# duckypad.net
KiCad netlist of a schematic drawn in EAGLE
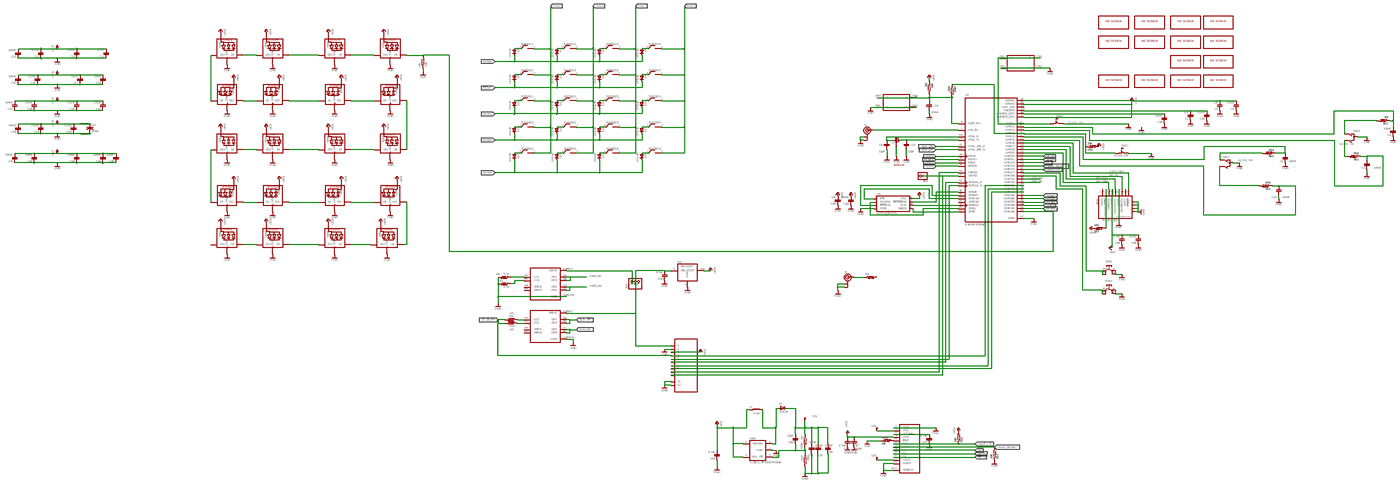
[diagram p0: schematic, sheet 1, overview]
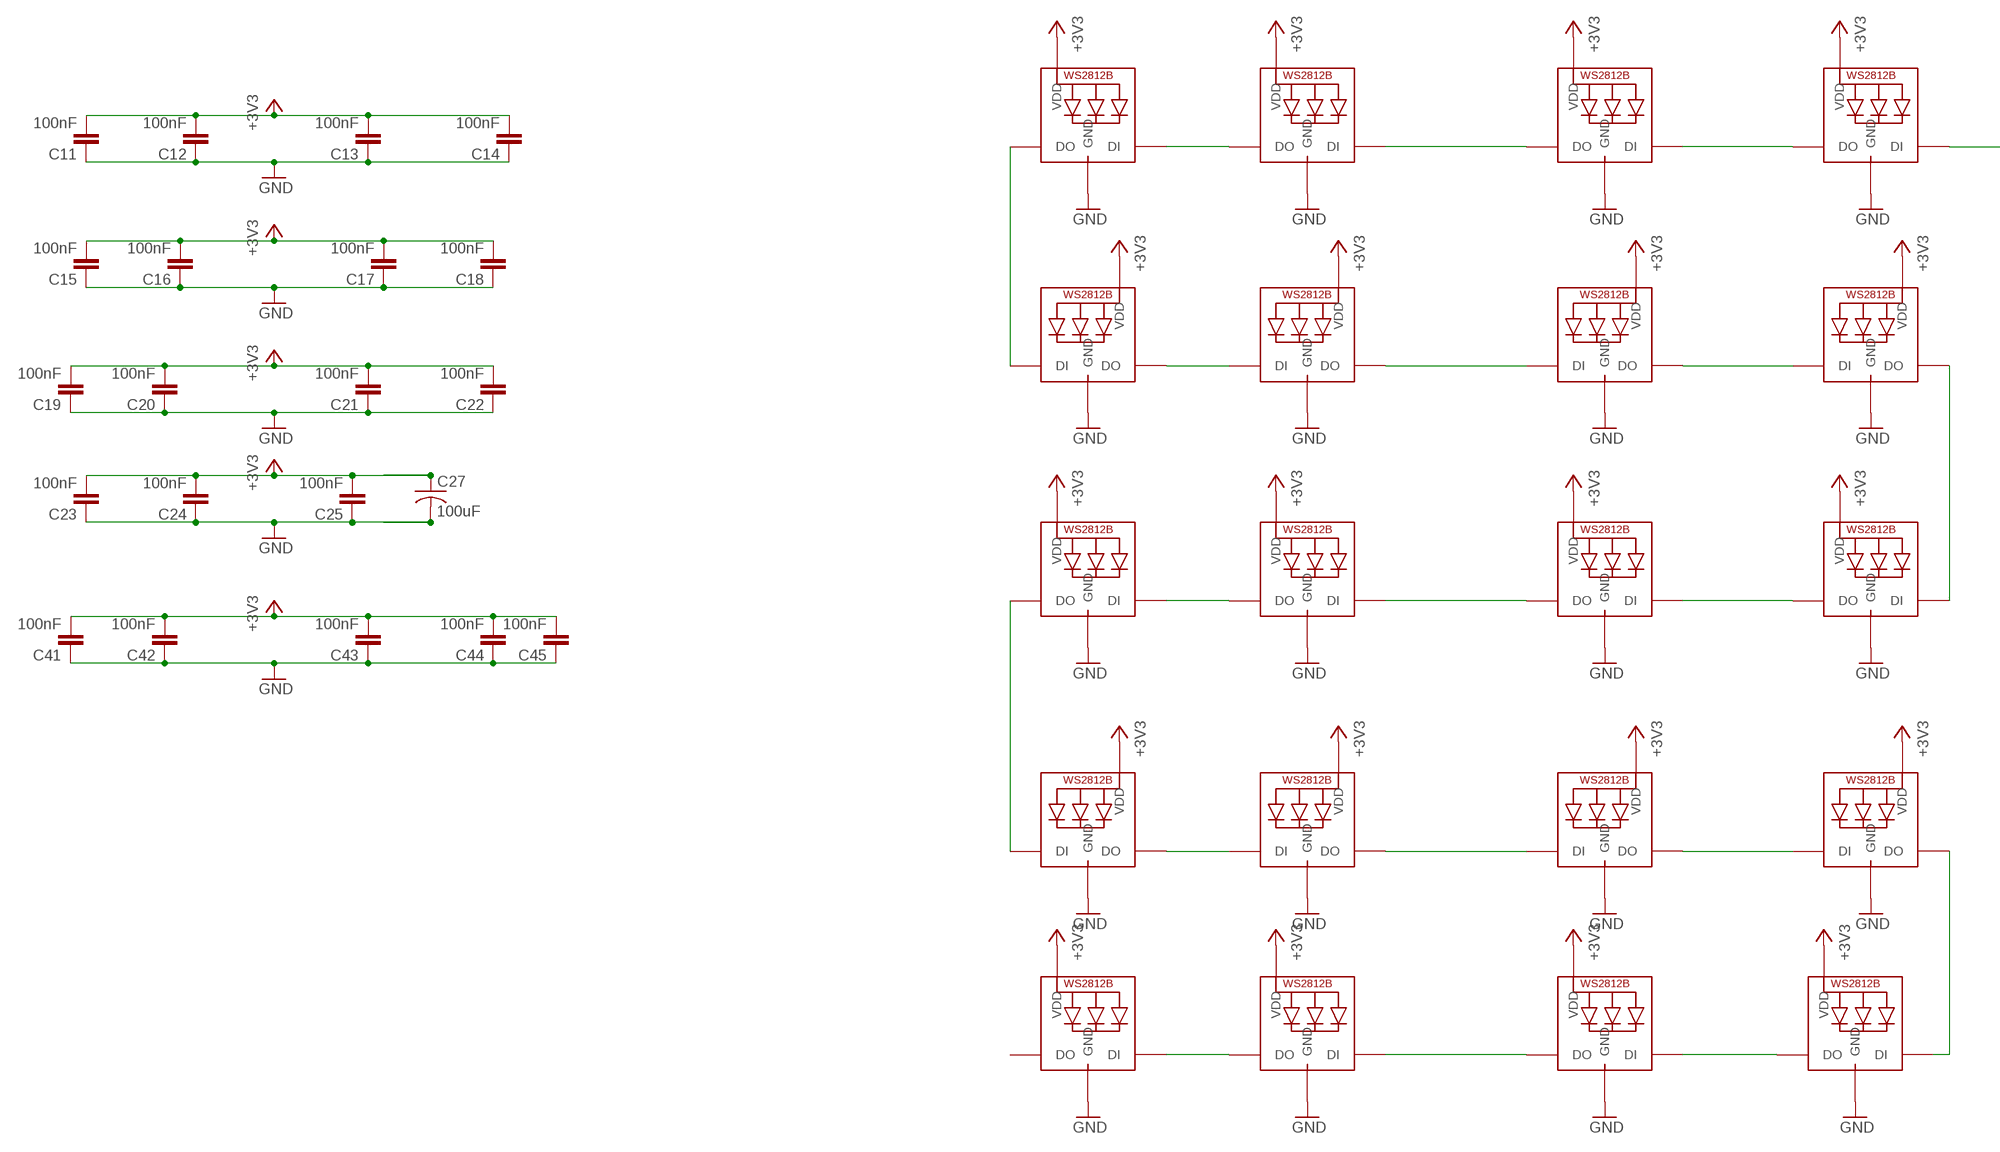
[diagram p1: schematic, sheet 1, part 1 of 4]
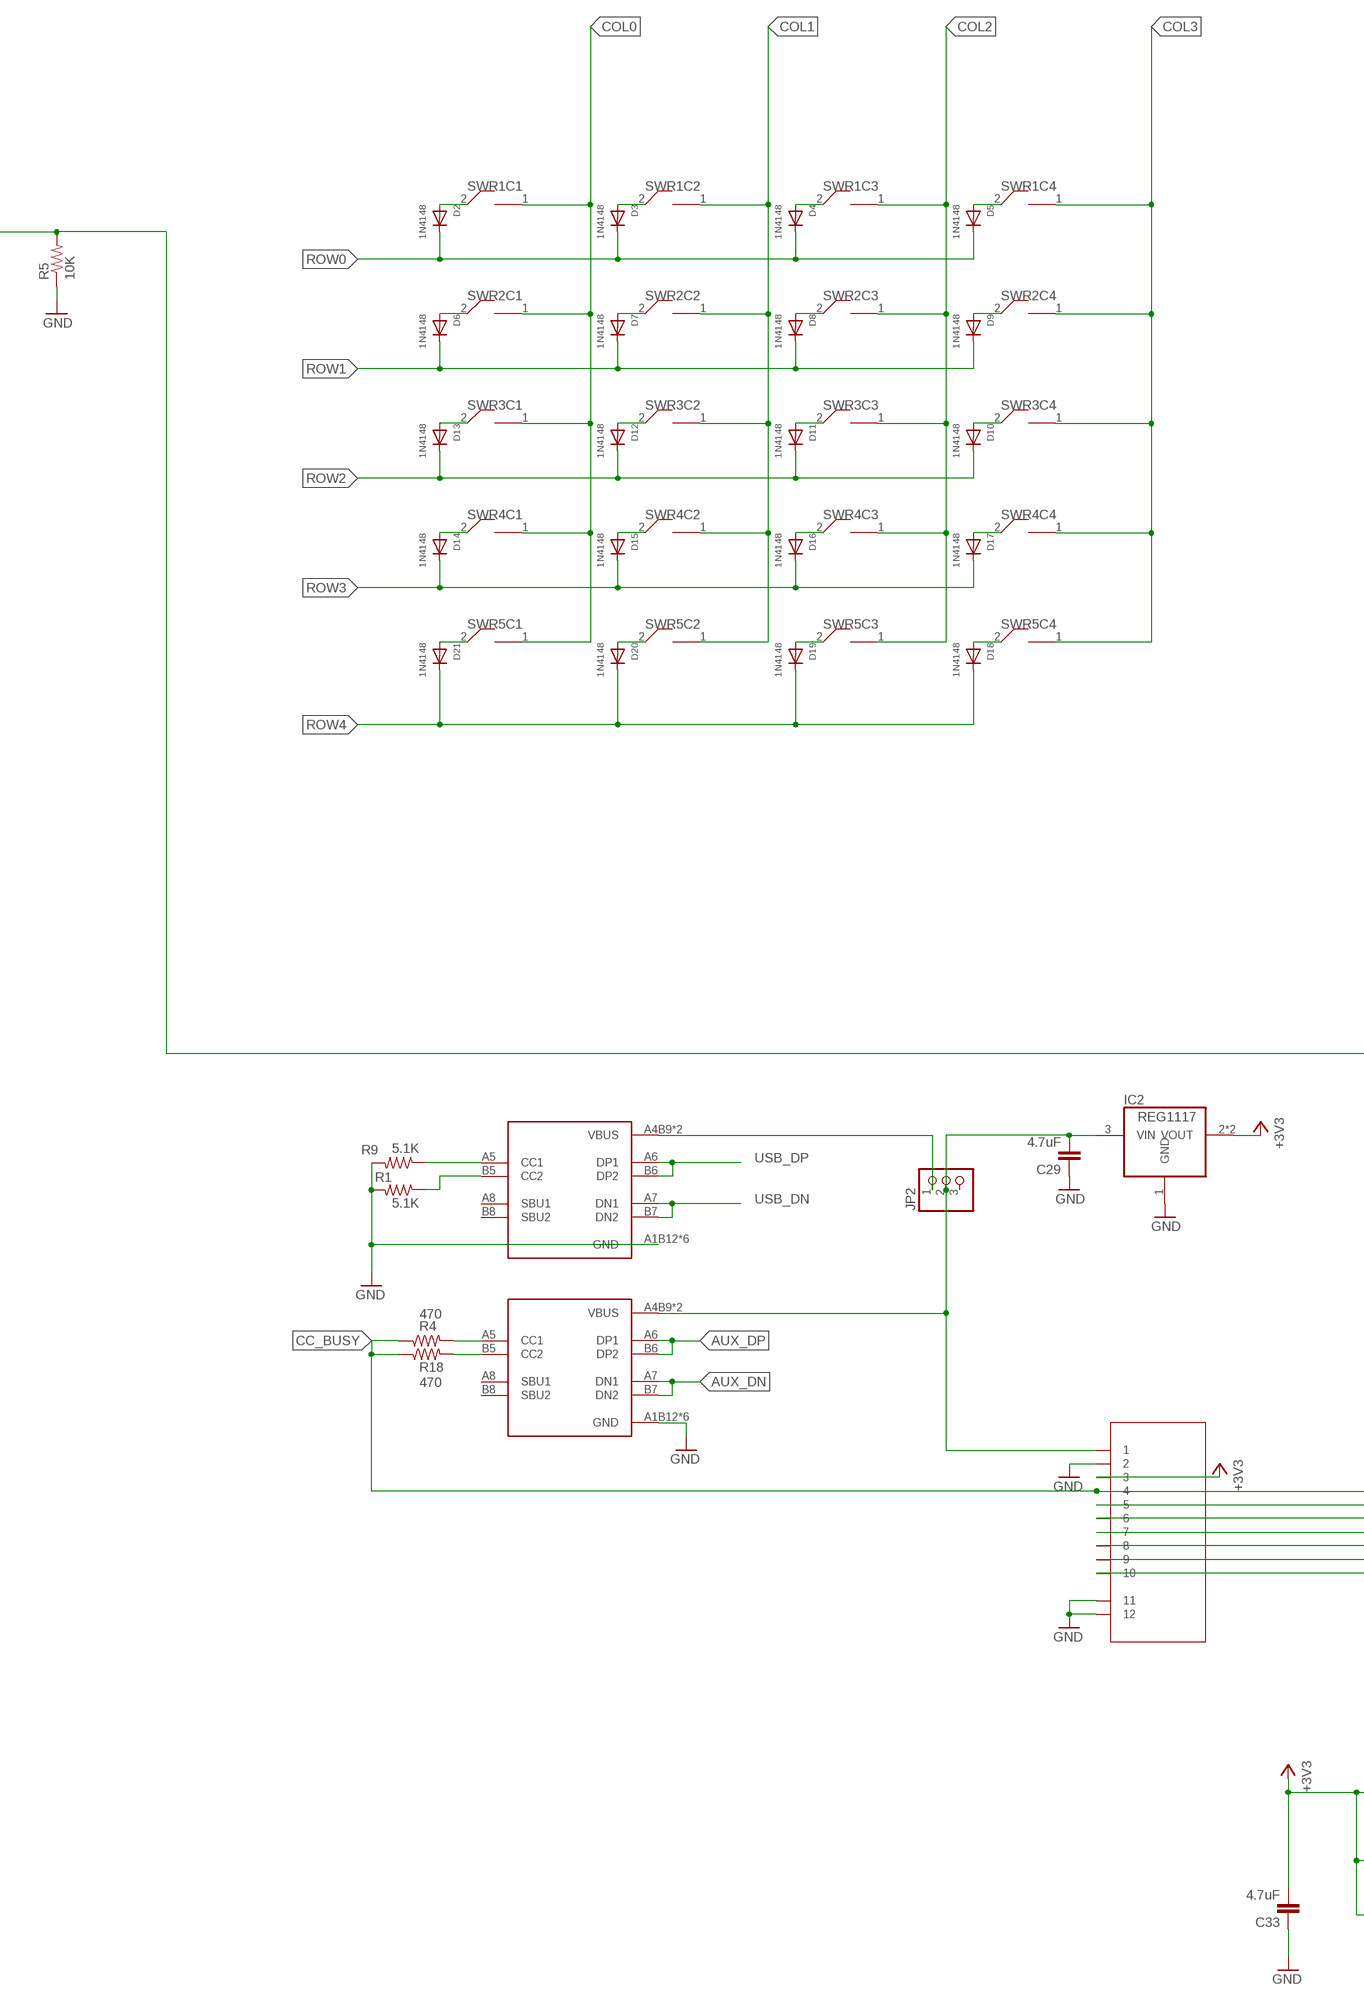
[diagram p2: schematic, sheet 1, part 2 of 4]
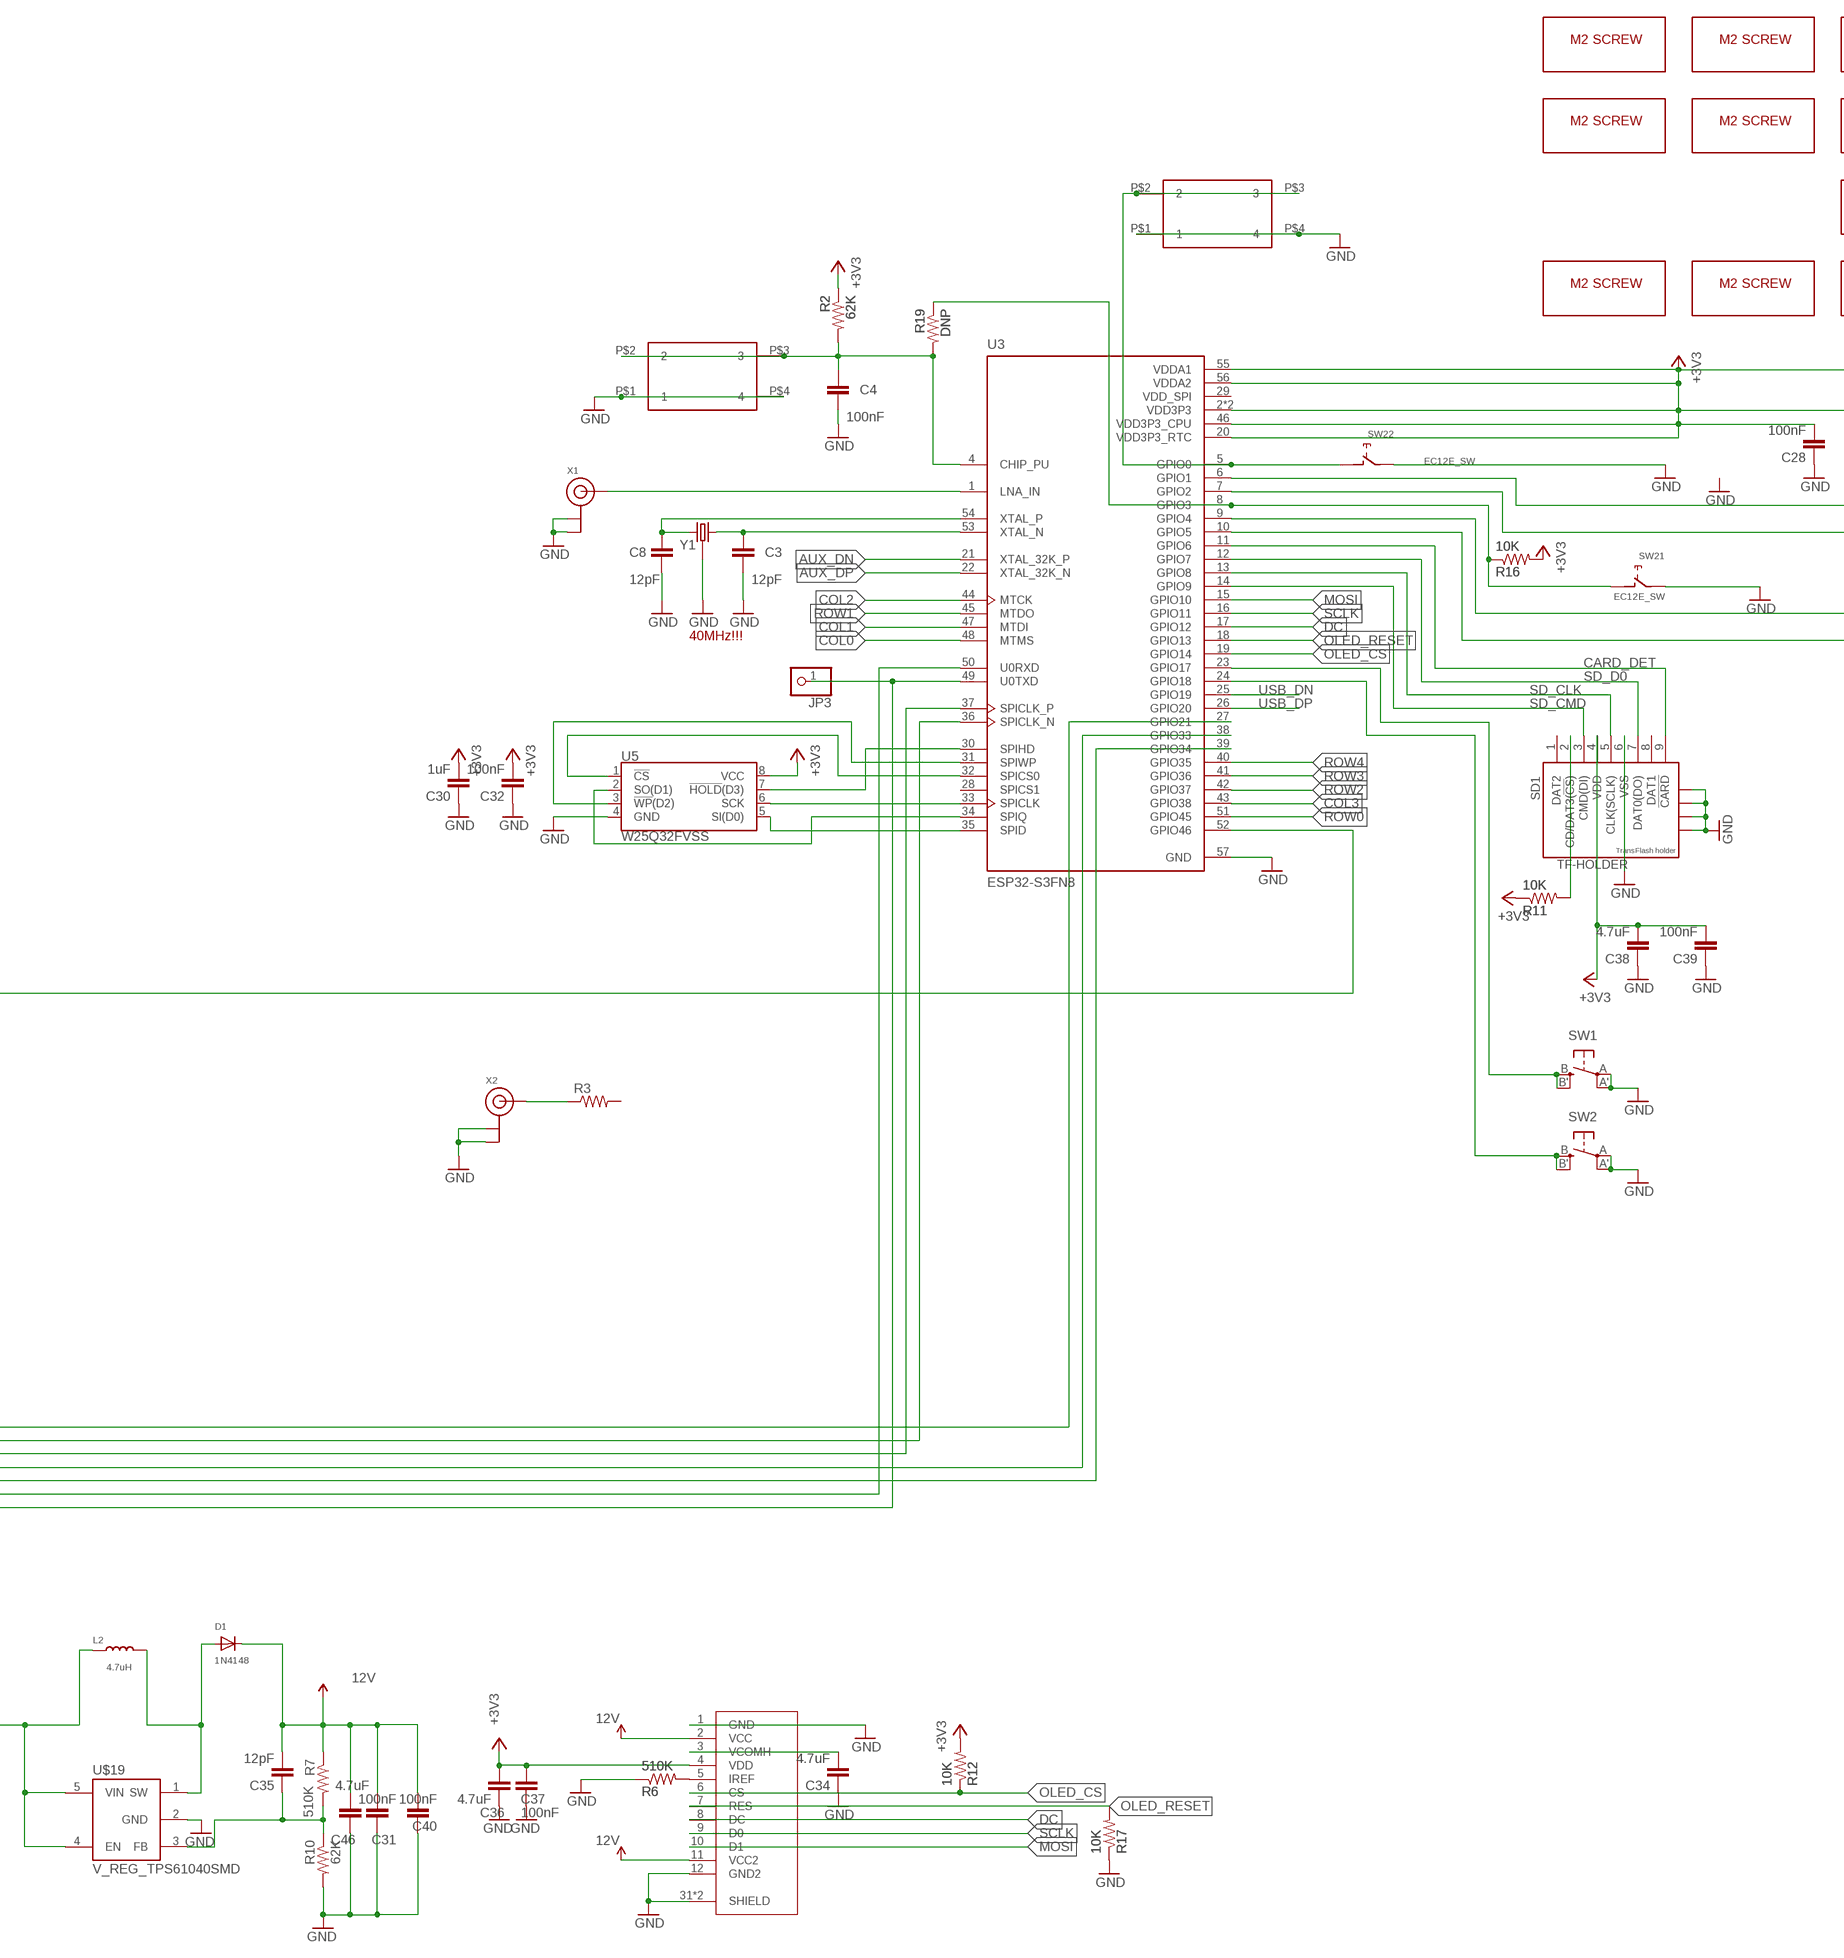
[diagram p3: schematic, sheet 1, part 3 of 4]
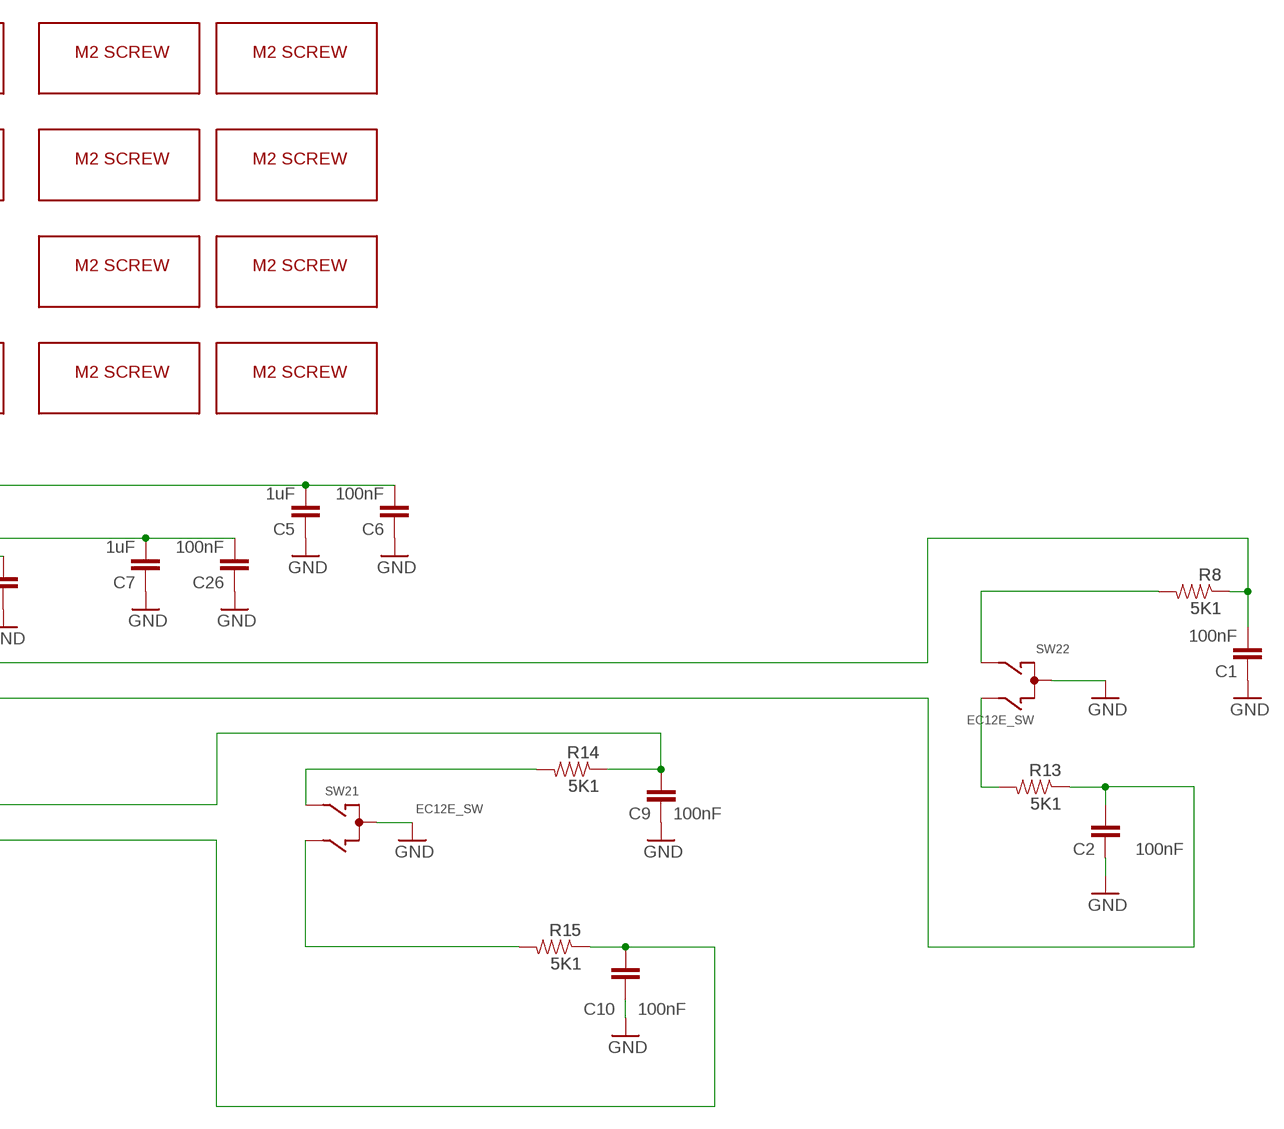
[diagram p4: schematic, sheet 1, part 4 of 4]

(export (version "E")
  (design (tool "Eeschema 10.0.6"))
  (components
    (comp (ref "C1")
      (value "100nF")
      (footprint "eagle-import:0805")
      (libsource (lib "eagle-import") (part "CAP0805"))
    )
    (comp (ref "C2")
      (value "100nF")
      (footprint "eagle-import:0805")
      (libsource (lib "eagle-import") (part "CAP0805"))
    )
    (comp (ref "C3")
      (value "12pF")
      (footprint "eagle-import:0805")
      (libsource (lib "eagle-import") (part "CAP0805"))
    )
    (comp (ref "C4")
      (value "100nF")
      (footprint "eagle-import:0805")
      (libsource (lib "eagle-import") (part "CAP0805"))
    )
    (comp (ref "C5")
      (value "1uF")
      (footprint "eagle-import:0805")
      (libsource (lib "eagle-import") (part "CAP0805"))
    )
    (comp (ref "C6")
      (value "100nF")
      (footprint "eagle-import:0805")
      (libsource (lib "eagle-import") (part "CAP0805"))
    )
    (comp (ref "C7")
      (value "1uF")
      (footprint "eagle-import:0805")
      (libsource (lib "eagle-import") (part "CAP0805"))
    )
    (comp (ref "C8")
      (value "12pF")
      (footprint "eagle-import:0805")
      (libsource (lib "eagle-import") (part "CAP0805"))
    )
    (comp (ref "C9")
      (value "100nF")
      (footprint "eagle-import:0805")
      (libsource (lib "eagle-import") (part "CAP0805"))
    )
    (comp (ref "C10")
      (value "100nF")
      (footprint "eagle-import:0805")
      (libsource (lib "eagle-import") (part "CAP0805"))
    )
    (comp (ref "C11")
      (value "100nF")
      (footprint "eagle-import:0805")
      (libsource (lib "eagle-import") (part "CAP0805"))
    )
    (comp (ref "C12")
      (value "100nF")
      (footprint "eagle-import:0805")
      (libsource (lib "eagle-import") (part "CAP0805"))
    )
    (comp (ref "C13")
      (value "100nF")
      (footprint "eagle-import:0805")
      (libsource (lib "eagle-import") (part "CAP0805"))
    )
    (comp (ref "C14")
      (value "100nF")
      (footprint "eagle-import:0805")
      (libsource (lib "eagle-import") (part "CAP0805"))
    )
    (comp (ref "C15")
      (value "100nF")
      (footprint "eagle-import:0805")
      (libsource (lib "eagle-import") (part "CAP0805"))
    )
    (comp (ref "C16")
      (value "100nF")
      (footprint "eagle-import:0805")
      (libsource (lib "eagle-import") (part "CAP0805"))
    )
    (comp (ref "C17")
      (value "100nF")
      (footprint "eagle-import:0805")
      (libsource (lib "eagle-import") (part "CAP0805"))
    )
    (comp (ref "C18")
      (value "100nF")
      (footprint "eagle-import:0805")
      (libsource (lib "eagle-import") (part "CAP0805"))
    )
    (comp (ref "C19")
      (value "100nF")
      (footprint "eagle-import:0805")
      (libsource (lib "eagle-import") (part "CAP0805"))
    )
    (comp (ref "C20")
      (value "100nF")
      (footprint "eagle-import:0805")
      (libsource (lib "eagle-import") (part "CAP0805"))
    )
    (comp (ref "C21")
      (value "100nF")
      (footprint "eagle-import:0805")
      (libsource (lib "eagle-import") (part "CAP0805"))
    )
    (comp (ref "C22")
      (value "100nF")
      (footprint "eagle-import:0805")
      (libsource (lib "eagle-import") (part "CAP0805"))
    )
    (comp (ref "C23")
      (value "100nF")
      (footprint "eagle-import:0805")
      (libsource (lib "eagle-import") (part "CAP0805"))
    )
    (comp (ref "C24")
      (value "100nF")
      (footprint "eagle-import:0805")
      (libsource (lib "eagle-import") (part "CAP0805"))
    )
    (comp (ref "C25")
      (value "100nF")
      (footprint "eagle-import:0805")
      (libsource (lib "eagle-import") (part "CAP0805"))
    )
    (comp (ref "C26")
      (value "100nF")
      (footprint "eagle-import:0805")
      (libsource (lib "eagle-import") (part "CAP0805"))
    )
    (comp (ref "C27")
      (value "100uF")
      (footprint "eagle-import:C1210")
      (libsource (lib "eagle-import") (part "C-USC1210"))
    )
    (comp (ref "C28")
      (value "100nF")
      (footprint "eagle-import:0805")
      (libsource (lib "eagle-import") (part "CAP0805"))
    )
    (comp (ref "C29")
      (value "4.7uF")
      (footprint "eagle-import:0805")
      (libsource (lib "eagle-import") (part "CAP0805"))
    )
    (comp (ref "C30")
      (value "1uF")
      (footprint "eagle-import:0805")
      (libsource (lib "eagle-import") (part "CAP0805"))
    )
    (comp (ref "C31")
      (value "100nF")
      (footprint "eagle-import:0805")
      (libsource (lib "eagle-import") (part "CAP0805"))
    )
    (comp (ref "C32")
      (value "100nF")
      (footprint "eagle-import:0805")
      (libsource (lib "eagle-import") (part "CAP0805"))
    )
    (comp (ref "C33")
      (value "4.7uF")
      (footprint "eagle-import:0805")
      (libsource (lib "eagle-import") (part "CAP0805"))
    )
    (comp (ref "C34")
      (value "4.7uF")
      (footprint "eagle-import:0805")
      (libsource (lib "eagle-import") (part "CAP0805"))
    )
    (comp (ref "C35")
      (value "12pF")
      (footprint "eagle-import:0805")
      (libsource (lib "eagle-import") (part "CAP0805"))
    )
    (comp (ref "C36")
      (value "4.7uF")
      (footprint "eagle-import:0805")
      (libsource (lib "eagle-import") (part "CAP0805"))
    )
    (comp (ref "C37")
      (value "100nF")
      (footprint "eagle-import:0805")
      (libsource (lib "eagle-import") (part "CAP0805"))
    )
    (comp (ref "C38")
      (value "4.7uF")
      (footprint "eagle-import:0805")
      (libsource (lib "eagle-import") (part "CAP0805"))
    )
    (comp (ref "C39")
      (value "100nF")
      (footprint "eagle-import:0805")
      (libsource (lib "eagle-import") (part "CAP0805"))
    )
    (comp (ref "C40")
      (value "100nF")
      (footprint "eagle-import:0805")
      (libsource (lib "eagle-import") (part "CAP0805"))
    )
    (comp (ref "C41")
      (value "100nF")
      (footprint "eagle-import:0805")
      (libsource (lib "eagle-import") (part "CAP0805"))
    )
    (comp (ref "C42")
      (value "100nF")
      (footprint "eagle-import:0805")
      (libsource (lib "eagle-import") (part "CAP0805"))
    )
    (comp (ref "C43")
      (value "100nF")
      (footprint "eagle-import:0805")
      (libsource (lib "eagle-import") (part "CAP0805"))
    )
    (comp (ref "C44")
      (value "100nF")
      (footprint "eagle-import:0805")
      (libsource (lib "eagle-import") (part "CAP0805"))
    )
    (comp (ref "C45")
      (value "100nF")
      (footprint "eagle-import:0805")
      (libsource (lib "eagle-import") (part "CAP0805"))
    )
    (comp (ref "C46")
      (value "4.7uF")
      (footprint "eagle-import:0805")
      (libsource (lib "eagle-import") (part "CAP0805"))
    )
    (comp (ref "D1")
      (value "1N4148")
      (footprint "eagle-import:ADAFRUIT_CHANGED_SOD-123")
      (libsource (lib "eagle-import") (part "ADAFRUIT_CHANGED_DIODESOD-123"))
    )
    (comp (ref "D2")
      (value "1N4148")
      (footprint "eagle-import:ADAFRUIT_CHANGED_SOD-123")
      (libsource (lib "eagle-import") (part "ADAFRUIT_CHANGED_DIODESOD-123"))
    )
    (comp (ref "D3")
      (value "1N4148")
      (footprint "eagle-import:ADAFRUIT_CHANGED_SOD-123")
      (libsource (lib "eagle-import") (part "ADAFRUIT_CHANGED_DIODESOD-123"))
    )
    (comp (ref "D4")
      (value "1N4148")
      (footprint "eagle-import:ADAFRUIT_CHANGED_SOD-123")
      (libsource (lib "eagle-import") (part "ADAFRUIT_CHANGED_DIODESOD-123"))
    )
    (comp (ref "D5")
      (value "1N4148")
      (footprint "eagle-import:ADAFRUIT_CHANGED_SOD-123")
      (libsource (lib "eagle-import") (part "ADAFRUIT_CHANGED_DIODESOD-123"))
    )
    (comp (ref "D6")
      (value "1N4148")
      (footprint "eagle-import:ADAFRUIT_CHANGED_SOD-123")
      (libsource (lib "eagle-import") (part "ADAFRUIT_CHANGED_DIODESOD-123"))
    )
    (comp (ref "D7")
      (value "1N4148")
      (footprint "eagle-import:ADAFRUIT_CHANGED_SOD-123")
      (libsource (lib "eagle-import") (part "ADAFRUIT_CHANGED_DIODESOD-123"))
    )
    (comp (ref "D8")
      (value "1N4148")
      (footprint "eagle-import:ADAFRUIT_CHANGED_SOD-123")
      (libsource (lib "eagle-import") (part "ADAFRUIT_CHANGED_DIODESOD-123"))
    )
    (comp (ref "D9")
      (value "1N4148")
      (footprint "eagle-import:ADAFRUIT_CHANGED_SOD-123")
      (libsource (lib "eagle-import") (part "ADAFRUIT_CHANGED_DIODESOD-123"))
    )
    (comp (ref "D10")
      (value "1N4148")
      (footprint "eagle-import:ADAFRUIT_CHANGED_SOD-123")
      (libsource (lib "eagle-import") (part "ADAFRUIT_CHANGED_DIODESOD-123"))
    )
    (comp (ref "D11")
      (value "1N4148")
      (footprint "eagle-import:ADAFRUIT_CHANGED_SOD-123")
      (libsource (lib "eagle-import") (part "ADAFRUIT_CHANGED_DIODESOD-123"))
    )
    (comp (ref "D12")
      (value "1N4148")
      (footprint "eagle-import:ADAFRUIT_CHANGED_SOD-123")
      (libsource (lib "eagle-import") (part "ADAFRUIT_CHANGED_DIODESOD-123"))
    )
    (comp (ref "D13")
      (value "1N4148")
      (footprint "eagle-import:ADAFRUIT_CHANGED_SOD-123")
      (libsource (lib "eagle-import") (part "ADAFRUIT_CHANGED_DIODESOD-123"))
    )
    (comp (ref "D14")
      (value "1N4148")
      (footprint "eagle-import:ADAFRUIT_CHANGED_SOD-123")
      (libsource (lib "eagle-import") (part "ADAFRUIT_CHANGED_DIODESOD-123"))
    )
    (comp (ref "D15")
      (value "1N4148")
      (footprint "eagle-import:ADAFRUIT_CHANGED_SOD-123")
      (libsource (lib "eagle-import") (part "ADAFRUIT_CHANGED_DIODESOD-123"))
    )
    (comp (ref "D16")
      (value "1N4148")
      (footprint "eagle-import:ADAFRUIT_CHANGED_SOD-123")
      (libsource (lib "eagle-import") (part "ADAFRUIT_CHANGED_DIODESOD-123"))
    )
    (comp (ref "D17")
      (value "1N4148")
      (footprint "eagle-import:ADAFRUIT_CHANGED_SOD-123")
      (libsource (lib "eagle-import") (part "ADAFRUIT_CHANGED_DIODESOD-123"))
    )
    (comp (ref "D18")
      (value "1N4148")
      (footprint "eagle-import:ADAFRUIT_CHANGED_SOD-123")
      (libsource (lib "eagle-import") (part "ADAFRUIT_CHANGED_DIODESOD-123"))
    )
    (comp (ref "D19")
      (value "1N4148")
      (footprint "eagle-import:ADAFRUIT_CHANGED_SOD-123")
      (libsource (lib "eagle-import") (part "ADAFRUIT_CHANGED_DIODESOD-123"))
    )
    (comp (ref "D20")
      (value "1N4148")
      (footprint "eagle-import:ADAFRUIT_CHANGED_SOD-123")
      (libsource (lib "eagle-import") (part "ADAFRUIT_CHANGED_DIODESOD-123"))
    )
    (comp (ref "D21")
      (value "1N4148")
      (footprint "eagle-import:ADAFRUIT_CHANGED_SOD-123")
      (libsource (lib "eagle-import") (part "ADAFRUIT_CHANGED_DIODESOD-123"))
    )
    (comp (ref "IC2")
      (value "REG1117")
      (footprint "eagle-import:SOT223")
      (libsource (lib "eagle-import") (part "REG1117"))
    )
    (comp (ref "JP2")
      (value "PINHD-1X3CB")
      (footprint "eagle-import:1X03-CLEANBIG")
      (libsource (lib "eagle-import") (part "PINHD-1X3CB"))
    )
    (comp (ref "JP3")
      (value "PINHD-1X1CB")
      (footprint "eagle-import:1X01-CLEANBIG")
      (libsource (lib "eagle-import") (part "PINHD-1X1CB"))
    )
    (comp (ref "L2")
      (value "4.7uH")
      (footprint "eagle-import:L4030")
      (libsource (lib "eagle-import") (part "L-4030"))
    )
    (comp (ref "LED_R1C1")
      (value "WS2812B")
      (footprint "eagle-import:REVERSE_MNT")
      (libsource (lib "eagle-import") (part "WS2812B"))
    )
    (comp (ref "LED_R1C2")
      (value "WS2812B")
      (footprint "eagle-import:REVERSE_MNT")
      (libsource (lib "eagle-import") (part "WS2812B"))
    )
    (comp (ref "LED_R1C3")
      (value "WS2812B")
      (footprint "eagle-import:REVERSE_MNT")
      (libsource (lib "eagle-import") (part "WS2812B"))
    )
    (comp (ref "LED_R1C4")
      (value "WS2812B")
      (footprint "eagle-import:REVERSE_MNT")
      (libsource (lib "eagle-import") (part "WS2812B"))
    )
    (comp (ref "LED_R2C1")
      (value "WS2812B")
      (footprint "eagle-import:REVERSE_MNT")
      (libsource (lib "eagle-import") (part "WS2812B"))
    )
    (comp (ref "LED_R2C2")
      (value "WS2812B")
      (footprint "eagle-import:REVERSE_MNT")
      (libsource (lib "eagle-import") (part "WS2812B"))
    )
    (comp (ref "LED_R2C3")
      (value "WS2812B")
      (footprint "eagle-import:REVERSE_MNT")
      (libsource (lib "eagle-import") (part "WS2812B"))
    )
    (comp (ref "LED_R2C4")
      (value "WS2812B")
      (footprint "eagle-import:REVERSE_MNT")
      (libsource (lib "eagle-import") (part "WS2812B"))
    )
    (comp (ref "LED_R3C1")
      (value "WS2812B")
      (footprint "eagle-import:REVERSE_MNT")
      (libsource (lib "eagle-import") (part "WS2812B"))
    )
    (comp (ref "LED_R3C2")
      (value "WS2812B")
      (footprint "eagle-import:REVERSE_MNT")
      (libsource (lib "eagle-import") (part "WS2812B"))
    )
    (comp (ref "LED_R3C3")
      (value "WS2812B")
      (footprint "eagle-import:REVERSE_MNT")
      (libsource (lib "eagle-import") (part "WS2812B"))
    )
    (comp (ref "LED_R3C4")
      (value "WS2812B")
      (footprint "eagle-import:REVERSE_MNT")
      (libsource (lib "eagle-import") (part "WS2812B"))
    )
    (comp (ref "LED_R4C1")
      (value "WS2812B")
      (footprint "eagle-import:REVERSE_MNT")
      (libsource (lib "eagle-import") (part "WS2812B"))
    )
    (comp (ref "LED_R4C2")
      (value "WS2812B")
      (footprint "eagle-import:REVERSE_MNT")
      (libsource (lib "eagle-import") (part "WS2812B"))
    )
    (comp (ref "LED_R4C3")
      (value "WS2812B")
      (footprint "eagle-import:REVERSE_MNT")
      (libsource (lib "eagle-import") (part "WS2812B"))
    )
    (comp (ref "LED_R4C4")
      (value "WS2812B")
      (footprint "eagle-import:REVERSE_MNT")
      (libsource (lib "eagle-import") (part "WS2812B"))
    )
    (comp (ref "LED_R5C1")
      (value "WS2812B")
      (footprint "eagle-import:REVERSE_MNT")
      (libsource (lib "eagle-import") (part "WS2812B"))
    )
    (comp (ref "LED_R5C2")
      (value "WS2812B")
      (footprint "eagle-import:REVERSE_MNT")
      (libsource (lib "eagle-import") (part "WS2812B"))
    )
    (comp (ref "LED_R5C3")
      (value "WS2812B")
      (footprint "eagle-import:REVERSE_MNT")
      (libsource (lib "eagle-import") (part "WS2812B"))
    )
    (comp (ref "LED_R5C4")
      (value "WS2812B")
      (footprint "eagle-import:REVERSE_MNT")
      (libsource (lib "eagle-import") (part "WS2812B"))
    )
    (comp (ref "R1")
      (value "5.1K")
      (footprint "eagle-import:0805")
      (libsource (lib "eagle-import") (part "joyAnalog_RESISTOR0805-RES"))
    )
    (comp (ref "R2")
      (value "62K")
      (footprint "eagle-import:0805")
      (libsource (lib "eagle-import") (part "joyAnalog_RESISTOR0805-RES"))
    )
    (comp (ref "R3")
      (value "R-US_R2010")
      (footprint "eagle-import:R2010")
      (libsource (lib "eagle-import") (part "R-US_R2010"))
    )
    (comp (ref "R4")
      (value "470")
      (footprint "eagle-import:0805")
      (libsource (lib "eagle-import") (part "joyAnalog_RESISTOR0805-RES"))
    )
    (comp (ref "R5")
      (value "10K")
      (footprint "eagle-import:0805")
      (libsource (lib "eagle-import") (part "RESISTOR0805-RES"))
    )
    (comp (ref "R6")
      (value "510K")
      (footprint "eagle-import:0805")
      (libsource (lib "eagle-import") (part "joyAnalog_RESISTOR0805-RES"))
    )
    (comp (ref "R7")
      (value "510K")
      (footprint "eagle-import:0805")
      (libsource (lib "eagle-import") (part "joyAnalog_RESISTOR0805-RES"))
    )
    (comp (ref "R8")
      (value "5K1")
      (footprint "eagle-import:0805")
      (libsource (lib "eagle-import") (part "joyAnalog_RESISTOR0805-RES"))
    )
    (comp (ref "R9")
      (value "5.1K")
      (footprint "eagle-import:0805")
      (libsource (lib "eagle-import") (part "joyAnalog_RESISTOR0805-RES"))
    )
    (comp (ref "R10")
      (value "62K")
      (footprint "eagle-import:0805")
      (libsource (lib "eagle-import") (part "joyAnalog_RESISTOR0805-RES"))
    )
    (comp (ref "R11")
      (value "10K")
      (footprint "eagle-import:0805")
      (libsource (lib "eagle-import") (part "joyAnalog_RESISTOR0805-RES"))
    )
    (comp (ref "R12")
      (value "10K")
      (footprint "eagle-import:0805")
      (libsource (lib "eagle-import") (part "joyAnalog_RESISTOR0805-RES"))
    )
    (comp (ref "R13")
      (value "5K1")
      (footprint "eagle-import:0805")
      (libsource (lib "eagle-import") (part "joyAnalog_RESISTOR0805-RES"))
    )
    (comp (ref "R14")
      (value "5K1")
      (footprint "eagle-import:0805")
      (libsource (lib "eagle-import") (part "joyAnalog_RESISTOR0805-RES"))
    )
    (comp (ref "R15")
      (value "5K1")
      (footprint "eagle-import:0805")
      (libsource (lib "eagle-import") (part "joyAnalog_RESISTOR0805-RES"))
    )
    (comp (ref "R16")
      (value "10K")
      (footprint "eagle-import:0805")
      (libsource (lib "eagle-import") (part "joyAnalog_RESISTOR0805-RES"))
    )
    (comp (ref "R17")
      (value "10K")
      (footprint "eagle-import:0805")
      (libsource (lib "eagle-import") (part "joyAnalog_RESISTOR0805-RES"))
    )
    (comp (ref "R18")
      (value "470")
      (footprint "eagle-import:0805")
      (libsource (lib "eagle-import") (part "joyAnalog_RESISTOR0805-RES"))
    )
    (comp (ref "R19")
      (value "DNP")
      (footprint "eagle-import:0805")
      (libsource (lib "eagle-import") (part "joyAnalog_RESISTOR0805-RES"))
    )
    (comp (ref "SD1")
      (value "TF-HOLDER")
      (footprint "eagle-import:TF-PULL")
      (libsource (lib "eagle-import") (part "TF-HOLDER"))
    )
    (comp (ref "SW1")
      (value "SPST_TACT-EVQQ2")
      (footprint "eagle-import:EVQ-Q2")
      (libsource (lib "eagle-import") (part "SPST_TACT-EVQQ2"))
    )
    (comp (ref "SW2")
      (value "SPST_TACT-EVQQ2")
      (footprint "eagle-import:EVQ-Q2")
      (libsource (lib "eagle-import") (part "SPST_TACT-EVQQ2"))
    )
    (comp (ref "SW3")
      (value "324_SW324_SWITCH_FOOT_HOLE")
      (footprint "eagle-import:342_SWICH_FOOT_HOLE")
      (libsource (lib "eagle-import") (part "324_SW324_SWITCH_FOOT_HOLE"))
    )
    (comp (ref "SW4")
      (value "324_SW324_SWITCH_FOOT_HOLE")
      (footprint "eagle-import:342_SWICH_FOOT_HOLE")
      (libsource (lib "eagle-import") (part "324_SW324_SWITCH_FOOT_HOLE"))
    )
    (comp (ref "SW21")
      (value "EC12E_SW")
      (footprint "eagle-import:ALPS_EC12E_SW")
      (fields (field (name "MPN") "EC12E2424407"))
      (libsource (lib "eagle-import") (part "EC12E_SW"))
    )
    (comp (ref "SW22")
      (value "EC12E_SW")
      (footprint "eagle-import:ALPS_EC12E_SW")
      (fields (field (name "MPN") "EC12E2424407"))
      (libsource (lib "eagle-import") (part "EC12E_SW"))
    )
    (comp (ref "SWR1C1")
      (value "KAILH_SWITCH_SOCKET_KAILH_SWITCH_SOCKET")
      (footprint "eagle-import:KAILH_SWITCH_SOCKET_SWITCH_SOCKET")
      (libsource (lib "eagle-import") (part "KAILH_SWITCH_SOCKET_KAILH_SWITCH_SOCKET"))
    )
    (comp (ref "SWR1C2")
      (value "KAILH_SWITCH_SOCKET_KAILH_SWITCH_SOCKET")
      (footprint "eagle-import:KAILH_SWITCH_SOCKET_SWITCH_SOCKET")
      (libsource (lib "eagle-import") (part "KAILH_SWITCH_SOCKET_KAILH_SWITCH_SOCKET"))
    )
    (comp (ref "SWR1C3")
      (value "KAILH_SWITCH_SOCKET_KAILH_SWITCH_SOCKET")
      (footprint "eagle-import:KAILH_SWITCH_SOCKET_SWITCH_SOCKET")
      (libsource (lib "eagle-import") (part "KAILH_SWITCH_SOCKET_KAILH_SWITCH_SOCKET"))
    )
    (comp (ref "SWR1C4")
      (value "KAILH_SWITCH_SOCKET_KAILH_SWITCH_SOCKET")
      (footprint "eagle-import:KAILH_SWITCH_SOCKET_SWITCH_SOCKET")
      (libsource (lib "eagle-import") (part "KAILH_SWITCH_SOCKET_KAILH_SWITCH_SOCKET"))
    )
    (comp (ref "SWR2C1")
      (value "KAILH_SWITCH_SOCKET_KAILH_SWITCH_SOCKET")
      (footprint "eagle-import:KAILH_SWITCH_SOCKET_SWITCH_SOCKET")
      (libsource (lib "eagle-import") (part "KAILH_SWITCH_SOCKET_KAILH_SWITCH_SOCKET"))
    )
    (comp (ref "SWR2C2")
      (value "KAILH_SWITCH_SOCKET_KAILH_SWITCH_SOCKET")
      (footprint "eagle-import:KAILH_SWITCH_SOCKET_SWITCH_SOCKET")
      (libsource (lib "eagle-import") (part "KAILH_SWITCH_SOCKET_KAILH_SWITCH_SOCKET"))
    )
    (comp (ref "SWR2C3")
      (value "KAILH_SWITCH_SOCKET_KAILH_SWITCH_SOCKET")
      (footprint "eagle-import:KAILH_SWITCH_SOCKET_SWITCH_SOCKET")
      (libsource (lib "eagle-import") (part "KAILH_SWITCH_SOCKET_KAILH_SWITCH_SOCKET"))
    )
    (comp (ref "SWR2C4")
      (value "KAILH_SWITCH_SOCKET_KAILH_SWITCH_SOCKET")
      (footprint "eagle-import:KAILH_SWITCH_SOCKET_SWITCH_SOCKET")
      (libsource (lib "eagle-import") (part "KAILH_SWITCH_SOCKET_KAILH_SWITCH_SOCKET"))
    )
    (comp (ref "SWR3C1")
      (value "KAILH_SWITCH_SOCKET_KAILH_SWITCH_SOCKET")
      (footprint "eagle-import:KAILH_SWITCH_SOCKET_SWITCH_SOCKET")
      (libsource (lib "eagle-import") (part "KAILH_SWITCH_SOCKET_KAILH_SWITCH_SOCKET"))
    )
    (comp (ref "SWR3C2")
      (value "KAILH_SWITCH_SOCKET_KAILH_SWITCH_SOCKET")
      (footprint "eagle-import:KAILH_SWITCH_SOCKET_SWITCH_SOCKET")
      (libsource (lib "eagle-import") (part "KAILH_SWITCH_SOCKET_KAILH_SWITCH_SOCKET"))
    )
    (comp (ref "SWR3C3")
      (value "KAILH_SWITCH_SOCKET_KAILH_SWITCH_SOCKET")
      (footprint "eagle-import:KAILH_SWITCH_SOCKET_SWITCH_SOCKET")
      (libsource (lib "eagle-import") (part "KAILH_SWITCH_SOCKET_KAILH_SWITCH_SOCKET"))
    )
    (comp (ref "SWR3C4")
      (value "KAILH_SWITCH_SOCKET_KAILH_SWITCH_SOCKET")
      (footprint "eagle-import:KAILH_SWITCH_SOCKET_SWITCH_SOCKET")
      (libsource (lib "eagle-import") (part "KAILH_SWITCH_SOCKET_KAILH_SWITCH_SOCKET"))
    )
    (comp (ref "SWR4C1")
      (value "KAILH_SWITCH_SOCKET_KAILH_SWITCH_SOCKET")
      (footprint "eagle-import:KAILH_SWITCH_SOCKET_SWITCH_SOCKET")
      (libsource (lib "eagle-import") (part "KAILH_SWITCH_SOCKET_KAILH_SWITCH_SOCKET"))
    )
    (comp (ref "SWR4C2")
      (value "KAILH_SWITCH_SOCKET_KAILH_SWITCH_SOCKET")
      (footprint "eagle-import:KAILH_SWITCH_SOCKET_SWITCH_SOCKET")
      (libsource (lib "eagle-import") (part "KAILH_SWITCH_SOCKET_KAILH_SWITCH_SOCKET"))
    )
    (comp (ref "SWR4C3")
      (value "KAILH_SWITCH_SOCKET_KAILH_SWITCH_SOCKET")
      (footprint "eagle-import:KAILH_SWITCH_SOCKET_SWITCH_SOCKET")
      (libsource (lib "eagle-import") (part "KAILH_SWITCH_SOCKET_KAILH_SWITCH_SOCKET"))
    )
    (comp (ref "SWR4C4")
      (value "KAILH_SWITCH_SOCKET_KAILH_SWITCH_SOCKET")
      (footprint "eagle-import:KAILH_SWITCH_SOCKET_SWITCH_SOCKET")
      (libsource (lib "eagle-import") (part "KAILH_SWITCH_SOCKET_KAILH_SWITCH_SOCKET"))
    )
    (comp (ref "SWR5C1")
      (value "KAILH_SWITCH_SOCKET_KAILH_SWITCH_SOCKET")
      (footprint "eagle-import:KAILH_SWITCH_SOCKET_SWITCH_SOCKET")
      (libsource (lib "eagle-import") (part "KAILH_SWITCH_SOCKET_KAILH_SWITCH_SOCKET"))
    )
    (comp (ref "SWR5C2")
      (value "KAILH_SWITCH_SOCKET_KAILH_SWITCH_SOCKET")
      (footprint "eagle-import:KAILH_SWITCH_SOCKET_SWITCH_SOCKET")
      (libsource (lib "eagle-import") (part "KAILH_SWITCH_SOCKET_KAILH_SWITCH_SOCKET"))
    )
    (comp (ref "SWR5C3")
      (value "KAILH_SWITCH_SOCKET_KAILH_SWITCH_SOCKET")
      (footprint "eagle-import:KAILH_SWITCH_SOCKET_SWITCH_SOCKET")
      (libsource (lib "eagle-import") (part "KAILH_SWITCH_SOCKET_KAILH_SWITCH_SOCKET"))
    )
    (comp (ref "SWR5C4")
      (value "KAILH_SWITCH_SOCKET_KAILH_SWITCH_SOCKET")
      (footprint "eagle-import:KAILH_SWITCH_SOCKET_SWITCH_SOCKET")
      (libsource (lib "eagle-import") (part "KAILH_SWITCH_SOCKET_KAILH_SWITCH_SOCKET"))
    )
    (comp (ref "U$2")
      (value "OLED128")
      (footprint "eagle-import:LUL_UG-2864HSWEG01_1.3_WRAPAROUND")
      (libsource (lib "eagle-import") (part "OLED128"))
    )
    (comp (ref "U$3")
      (value "SH10P")
      (footprint "eagle-import:DUCKYPAD_SM12B-SSR-H-TB")
      (libsource (lib "eagle-import") (part "SH10P"))
    )
    (comp (ref "U$7")
      (value "M2_SCREW_DEV")
      (footprint "eagle-import:M2_SCREW_FOOT")
      (libsource (lib "eagle-import") (part "M2_SCREW_DEV"))
    )
    (comp (ref "U$8")
      (value "M2_SCREW_DEV")
      (footprint "eagle-import:M2_SCREW_FOOT")
      (libsource (lib "eagle-import") (part "M2_SCREW_DEV"))
    )
    (comp (ref "U$9")
      (value "M2_SCREW_DEV")
      (footprint "eagle-import:M2_SCREW_FOOT")
      (libsource (lib "eagle-import") (part "M2_SCREW_DEV"))
    )
    (comp (ref "U$10")
      (value "M2_SCREW_DEV")
      (footprint "eagle-import:M2_SCREW_FOOT")
      (libsource (lib "eagle-import") (part "M2_SCREW_DEV"))
    )
    (comp (ref "U$11")
      (value "M2_SCREW_DEV")
      (footprint "eagle-import:M2_SCREW_FOOT")
      (libsource (lib "eagle-import") (part "M2_SCREW_DEV"))
    )
    (comp (ref "U$12")
      (value "M2_SCREW_DEV")
      (footprint "eagle-import:M2_SCREW_FOOT")
      (libsource (lib "eagle-import") (part "M2_SCREW_DEV"))
    )
    (comp (ref "U$13")
      (value "M2_SCREW_DEV")
      (footprint "eagle-import:M2_SCREW_FOOT")
      (libsource (lib "eagle-import") (part "M2_SCREW_DEV"))
    )
    (comp (ref "U$14")
      (value "M2_SCREW_DEV")
      (footprint "eagle-import:M2_SCREW_FOOT")
      (libsource (lib "eagle-import") (part "M2_SCREW_DEV"))
    )
    (comp (ref "U$15")
      (value "M2_SCREW_DEV")
      (footprint "eagle-import:M2_SCREW_FOOT")
      (libsource (lib "eagle-import") (part "M2_SCREW_DEV"))
    )
    (comp (ref "U$16")
      (value "M2_SCREW_DEV")
      (footprint "eagle-import:M2_SCREW_FOOT")
      (libsource (lib "eagle-import") (part "M2_SCREW_DEV"))
    )
    (comp (ref "U$17")
      (value "M2_SCREW_DEV")
      (footprint "eagle-import:M2_SCREW_FOOT")
      (libsource (lib "eagle-import") (part "M2_SCREW_DEV"))
    )
    (comp (ref "U$19")
      (value "V_REG_TPS61040SMD")
      (footprint "eagle-import:SOT23-5")
      (libsource (lib "eagle-import") (part "V_REG_TPS61040SMD"))
    )
    (comp (ref "U$20")
      (value "M2_SCREW_DEV")
      (footprint "eagle-import:M2_SCREW_FOOT")
      (libsource (lib "eagle-import") (part "M2_SCREW_DEV"))
    )
    (comp (ref "U$21")
      (value "M2_SCREW_DEV")
      (footprint "eagle-import:M2_SCREW_FOOT")
      (libsource (lib "eagle-import") (part "M2_SCREW_DEV"))
    )
    (comp (ref "U$22")
      (value "M2_SCREW_DEV")
      (footprint "eagle-import:M2_SCREW_FOOT")
      (libsource (lib "eagle-import") (part "M2_SCREW_DEV"))
    )
    (comp (ref "U1")
      (value "USBC_16P")
      (footprint "eagle-import:USBC_16P_FOOT")
      (libsource (lib "eagle-import") (part "USBC_16P"))
    )
    (comp (ref "U2")
      (value "USBC_16P")
      (footprint "eagle-import:USBC_16P_FOOT")
      (libsource (lib "eagle-import") (part "USBC_16P"))
    )
    (comp (ref "U3")
      (value "ESP32-S3FN8")
      (footprint "eagle-import:QFN40P700X700X90-57N")
      (fields (field (name "MF") "Espressif Systems"))
      (libsource (lib "eagle-import") (part "ESP32-S3FN8"))
    )
    (comp (ref "U5")
      (value "W25Q32FVSS")
      (footprint "eagle-import:SOIC-8")
      (libsource (lib "eagle-import") (part "W25Q32FVSS"))
    )
    (comp (ref "X1")
      (value "ANTENNA_U.FL")
      (footprint "eagle-import:U.FL")
      (libsource (lib "eagle-import") (part "ANTENNA_U.FL"))
    )
    (comp (ref "X2")
      (value "ANTENNA_U.FL")
      (footprint "eagle-import:U.FL")
      (libsource (lib "eagle-import") (part "ANTENNA_U.FL"))
    )
    (comp (ref "Y1")
      (value "16MHz_12pF")
      (footprint "eagle-import:CRYSTAL-SMD-3.2X2.5MM")
      (libsource (lib "eagle-import") (part "CRYSTAL-26MHZSMD-3.2X2.5"))
    )
  )
  (nets
    (net (code "1") (name "+3V3") (class "Default")
      (node (ref "C11") (pin "2") (pinfunction "2_2") (pintype "passive"))
      (node (ref "C12") (pin "2") (pinfunction "2_2") (pintype "passive"))
      (node (ref "C13") (pin "2") (pinfunction "2_2") (pintype "passive"))
      (node (ref "C14") (pin "2") (pinfunction "2_2") (pintype "passive"))
      (node (ref "C15") (pin "2") (pinfunction "2_2") (pintype "passive"))
      (node (ref "C16") (pin "2") (pinfunction "2_2") (pintype "passive"))
      (node (ref "C17") (pin "2") (pinfunction "2_2") (pintype "passive"))
      (node (ref "C18") (pin "2") (pinfunction "2_2") (pintype "passive"))
      (node (ref "C19") (pin "2") (pinfunction "2_2") (pintype "passive"))
      (node (ref "C20") (pin "2") (pinfunction "2_2") (pintype "passive"))
      (node (ref "C21") (pin "2") (pinfunction "2_2") (pintype "passive"))
      (node (ref "C22") (pin "2") (pinfunction "2_2") (pintype "passive"))
      (node (ref "C23") (pin "2") (pinfunction "2_2") (pintype "passive"))
      (node (ref "C24") (pin "2") (pinfunction "2_2") (pintype "passive"))
      (node (ref "C25") (pin "2") (pinfunction "2_2") (pintype "passive"))
      (node (ref "C26") (pin "2") (pinfunction "2_2") (pintype "passive"))
      (node (ref "C27") (pin "1") (pinfunction "1_1") (pintype "passive"))
      (node (ref "C28") (pin "2") (pinfunction "2_2") (pintype "passive"))
      (node (ref "C30") (pin "2") (pinfunction "2_2") (pintype "passive"))
      (node (ref "C32") (pin "2") (pinfunction "2_2") (pintype "passive"))
      (node (ref "C33") (pin "2") (pinfunction "2_2") (pintype "passive"))
      (node (ref "C36") (pin "2") (pinfunction "2_2") (pintype "passive"))
      (node (ref "C37") (pin "2") (pinfunction "2_2") (pintype "passive"))
      (node (ref "C38") (pin "2") (pinfunction "2_2") (pintype "passive"))
      (node (ref "C39") (pin "2") (pinfunction "2_2") (pintype "passive"))
      (node (ref "C41") (pin "2") (pinfunction "2_2") (pintype "passive"))
      (node (ref "C42") (pin "2") (pinfunction "2_2") (pintype "passive"))
      (node (ref "C43") (pin "2") (pinfunction "2_2") (pintype "passive"))
      (node (ref "C44") (pin "2") (pinfunction "2_2") (pintype "passive"))
      (node (ref "C45") (pin "2") (pinfunction "2_2") (pintype "passive"))
      (node (ref "C5") (pin "2") (pinfunction "2_2") (pintype "passive"))
      (node (ref "C6") (pin "2") (pinfunction "2_2") (pintype "passive"))
      (node (ref "C7") (pin "2") (pinfunction "2_2") (pintype "passive"))
      (node (ref "IC2") (pin "2") (pinfunction "VOUT_2") (pintype "output"))
      (node (ref "IC2") (pin "4") (pinfunction "VOUT_4") (pintype "output"))
      (node (ref "L2") (pin "1") (pinfunction "1_1") (pintype "passive"))
      (node (ref "LED_R1C1") (pin "VDD") (pinfunction "VDD_VDD") (pintype "power_in"))
      (node (ref "LED_R1C2") (pin "VDD") (pinfunction "VDD_VDD") (pintype "power_in"))
      (node (ref "LED_R1C3") (pin "VDD") (pinfunction "VDD_VDD") (pintype "power_in"))
      (node (ref "LED_R1C4") (pin "VDD") (pinfunction "VDD_VDD") (pintype "power_in"))
      (node (ref "LED_R2C1") (pin "VDD") (pinfunction "VDD_VDD") (pintype "power_in"))
      (node (ref "LED_R2C2") (pin "VDD") (pinfunction "VDD_VDD") (pintype "power_in"))
      (node (ref "LED_R2C3") (pin "VDD") (pinfunction "VDD_VDD") (pintype "power_in"))
      (node (ref "LED_R2C4") (pin "VDD") (pinfunction "VDD_VDD") (pintype "power_in"))
      (node (ref "LED_R3C1") (pin "VDD") (pinfunction "VDD_VDD") (pintype "power_in"))
      (node (ref "LED_R3C2") (pin "VDD") (pinfunction "VDD_VDD") (pintype "power_in"))
      (node (ref "LED_R3C3") (pin "VDD") (pinfunction "VDD_VDD") (pintype "power_in"))
      (node (ref "LED_R3C4") (pin "VDD") (pinfunction "VDD_VDD") (pintype "power_in"))
      (node (ref "LED_R4C1") (pin "VDD") (pinfunction "VDD_VDD") (pintype "power_in"))
      (node (ref "LED_R4C2") (pin "VDD") (pinfunction "VDD_VDD") (pintype "power_in"))
      (node (ref "LED_R4C3") (pin "VDD") (pinfunction "VDD_VDD") (pintype "power_in"))
      (node (ref "LED_R4C4") (pin "VDD") (pinfunction "VDD_VDD") (pintype "power_in"))
      (node (ref "LED_R5C1") (pin "VDD") (pinfunction "VDD_VDD") (pintype "power_in"))
      (node (ref "LED_R5C2") (pin "VDD") (pinfunction "VDD_VDD") (pintype "power_in"))
      (node (ref "LED_R5C3") (pin "VDD") (pinfunction "VDD_VDD") (pintype "power_in"))
      (node (ref "LED_R5C4") (pin "VDD") (pinfunction "VDD_VDD") (pintype "power_in"))
      (node (ref "R11") (pin "1") (pinfunction "1_1") (pintype "passive"))
      (node (ref "R12") (pin "2") (pinfunction "2_2") (pintype "passive"))
      (node (ref "R16") (pin "2") (pinfunction "2_2") (pintype "passive"))
      (node (ref "R2") (pin "1") (pinfunction "1_1") (pintype "passive"))
      (node (ref "SD1") (pin "4") (pinfunction "VDD_4") (pintype "power_in"))
      (node (ref "U$19") (pin "4") (pinfunction "EN_4") (pintype "bidirectional"))
      (node (ref "U$19") (pin "5") (pinfunction "VIN_5") (pintype "bidirectional"))
      (node (ref "U$2") (pin "4") (pinfunction "VDD_4") (pintype "bidirectional"))
      (node (ref "U$3") (pin "3") (pinfunction "3_3") (pintype "passive"))
      (node (ref "U3") (pin "2") (pinfunction "VDD3P3_2") (pintype "power_in"))
      (node (ref "U3") (pin "20") (pinfunction "VDD3P3_RTC_20") (pintype "power_in"))
      (node (ref "U3") (pin "3") (pinfunction "VDD3P3_3") (pintype "power_in"))
      (node (ref "U3") (pin "46") (pinfunction "VDD3P3_CPU_46") (pintype "power_in"))
      (node (ref "U3") (pin "55") (pinfunction "VDDA1_55") (pintype "power_in"))
      (node (ref "U3") (pin "56") (pinfunction "VDDA2_56") (pintype "power_in"))
      (node (ref "U5") (pin "8") (pinfunction "VCC_8") (pintype "bidirectional"))
    )
    (net (code "2") (name "/CARD_DET") (class "Default")
      (node (ref "SD1") (pin "9") (pinfunction "~{CARD}_9") (pintype "passive"))
      (node (ref "U3") (pin "11") (pinfunction "GPIO6_11") (pintype "bidirectional"))
    )
    (net (code "3") (name "/SD_CLK") (class "Default")
      (node (ref "SD1") (pin "5") (pinfunction "CLK(SCLK)_5") (pintype "input"))
      (node (ref "U3") (pin "13") (pinfunction "GPIO8_13") (pintype "bidirectional"))
    )
    (net (code "4") (name "/SD_CMD") (class "Default")
      (node (ref "SD1") (pin "3") (pinfunction "CMD(DI)_3") (pintype "bidirectional"))
      (node (ref "U3") (pin "14") (pinfunction "GPIO9_14") (pintype "bidirectional"))
    )
    (net (code "5") (name "/SD_D0") (class "Default")
      (node (ref "SD1") (pin "7") (pinfunction "DAT0(DO)_7") (pintype "bidirectional"))
      (node (ref "U3") (pin "12") (pinfunction "GPIO7_12") (pintype "bidirectional"))
    )
    (net (code "6") (name "/USB_DN") (class "Default")
      (node (ref "U2") (pin "A7") (pinfunction "DN1_A7") (pintype "bidirectional"))
      (node (ref "U2") (pin "B7") (pinfunction "DN2_B7") (pintype "bidirectional"))
      (node (ref "U3") (pin "25") (pinfunction "GPIO19_25") (pintype "bidirectional"))
    )
    (net (code "7") (name "/USB_DP") (class "Default")
      (node (ref "U2") (pin "A6") (pinfunction "DP1_A6") (pintype "bidirectional"))
      (node (ref "U2") (pin "B6") (pinfunction "DP2_B6") (pintype "bidirectional"))
      (node (ref "U3") (pin "26") (pinfunction "GPIO20_26") (pintype "bidirectional"))
    )
    (net (code "8") (name "/VDD_SPI") (class "Default")
      (node (ref "U3") (pin "29") (pinfunction "VDD_SPI_29") (pintype "power_in"))
    )
    (net (code "9") (name "12V") (class "Default")
      (node (ref "C31") (pin "2") (pinfunction "2_2") (pintype "passive"))
      (node (ref "C35") (pin "2") (pinfunction "2_2") (pintype "passive"))
      (node (ref "C40") (pin "2") (pinfunction "2_2") (pintype "passive"))
      (node (ref "C46") (pin "2") (pinfunction "2_2") (pintype "passive"))
      (node (ref "D1") (pin "C") (pinfunction "C_C") (pintype "passive"))
      (node (ref "R7") (pin "1") (pinfunction "1_1") (pintype "passive"))
      (node (ref "U$2") (pin "11") (pinfunction "VCC2_11") (pintype "bidirectional"))
      (node (ref "U$2") (pin "2") (pinfunction "VCC_2") (pintype "bidirectional"))
    )
    (net (code "10") (name "AUX_DN") (class "Default")
      (node (ref "U1") (pin "A7") (pinfunction "DN1_A7") (pintype "bidirectional"))
      (node (ref "U1") (pin "B7") (pinfunction "DN2_B7") (pintype "bidirectional"))
      (node (ref "U3") (pin "21") (pinfunction "XTAL_32K_P_21") (pintype "bidirectional"))
    )
    (net (code "11") (name "AUX_DP") (class "Default")
      (node (ref "U1") (pin "A6") (pinfunction "DP1_A6") (pintype "bidirectional"))
      (node (ref "U1") (pin "B6") (pinfunction "DP2_B6") (pintype "bidirectional"))
      (node (ref "U3") (pin "22") (pinfunction "XTAL_32K_N_22") (pintype "bidirectional"))
    )
    (net (code "12") (name "CC_BUSY") (class "Default")
      (node (ref "R18") (pin "1") (pinfunction "1_1") (pintype "passive"))
      (node (ref "R4") (pin "1") (pinfunction "1_1") (pintype "passive"))
      (node (ref "U$3") (pin "4") (pinfunction "4_4") (pintype "passive"))
      (node (ref "U3") (pin "27") (pinfunction "GPIO21_27") (pintype "bidirectional"))
    )
    (net (code "13") (name "COL0") (class "Default")
      (node (ref "SWR1C1") (pin "1") (pinfunction "2_1") (pintype "passive"))
      (node (ref "SWR2C1") (pin "1") (pinfunction "2_1") (pintype "passive"))
      (node (ref "SWR3C1") (pin "1") (pinfunction "2_1") (pintype "passive"))
      (node (ref "SWR4C1") (pin "1") (pinfunction "2_1") (pintype "passive"))
      (node (ref "SWR5C1") (pin "1") (pinfunction "2_1") (pintype "passive"))
      (node (ref "U3") (pin "48") (pinfunction "MTMS_48") (pintype "bidirectional"))
    )
    (net (code "14") (name "COL1") (class "Default")
      (node (ref "SWR1C2") (pin "1") (pinfunction "2_1") (pintype "passive"))
      (node (ref "SWR2C2") (pin "1") (pinfunction "2_1") (pintype "passive"))
      (node (ref "SWR3C2") (pin "1") (pinfunction "2_1") (pintype "passive"))
      (node (ref "SWR4C2") (pin "1") (pinfunction "2_1") (pintype "passive"))
      (node (ref "SWR5C2") (pin "1") (pinfunction "2_1") (pintype "passive"))
      (node (ref "U3") (pin "47") (pinfunction "MTDI_47") (pintype "bidirectional"))
    )
    (net (code "15") (name "COL2") (class "Default")
      (node (ref "SWR1C3") (pin "1") (pinfunction "2_1") (pintype "passive"))
      (node (ref "SWR2C3") (pin "1") (pinfunction "2_1") (pintype "passive"))
      (node (ref "SWR3C3") (pin "1") (pinfunction "2_1") (pintype "passive"))
      (node (ref "SWR4C3") (pin "1") (pinfunction "2_1") (pintype "passive"))
      (node (ref "SWR5C3") (pin "1") (pinfunction "2_1") (pintype "passive"))
      (node (ref "U3") (pin "44") (pinfunction "MTCK_44") (pintype "bidirectional"))
    )
    (net (code "16") (name "COL3") (class "Default")
      (node (ref "SWR1C4") (pin "1") (pinfunction "2_1") (pintype "passive"))
      (node (ref "SWR2C4") (pin "1") (pinfunction "2_1") (pintype "passive"))
      (node (ref "SWR3C4") (pin "1") (pinfunction "2_1") (pintype "passive"))
      (node (ref "SWR4C4") (pin "1") (pinfunction "2_1") (pintype "passive"))
      (node (ref "SWR5C4") (pin "1") (pinfunction "2_1") (pintype "passive"))
      (node (ref "U3") (pin "43") (pinfunction "GPIO38_43") (pintype "bidirectional"))
    )
    (net (code "17") (name "DC") (class "Default")
      (node (ref "U$2") (pin "8") (pinfunction "DC_8") (pintype "bidirectional"))
      (node (ref "U3") (pin "17") (pinfunction "GPIO12_17") (pintype "bidirectional"))
    )
    (net (code "18") (name "GND") (class "Default")
      (node (ref "C1") (pin "1") (pinfunction "1_1") (pintype "passive"))
      (node (ref "C10") (pin "1") (pinfunction "1_1") (pintype "passive"))
      (node (ref "C11") (pin "1") (pinfunction "1_1") (pintype "passive"))
      (node (ref "C12") (pin "1") (pinfunction "1_1") (pintype "passive"))
      (node (ref "C13") (pin "1") (pinfunction "1_1") (pintype "passive"))
      (node (ref "C14") (pin "1") (pinfunction "1_1") (pintype "passive"))
      (node (ref "C15") (pin "1") (pinfunction "1_1") (pintype "passive"))
      (node (ref "C16") (pin "1") (pinfunction "1_1") (pintype "passive"))
      (node (ref "C17") (pin "1") (pinfunction "1_1") (pintype "passive"))
      (node (ref "C18") (pin "1") (pinfunction "1_1") (pintype "passive"))
      (node (ref "C19") (pin "1") (pinfunction "1_1") (pintype "passive"))
      (node (ref "C2") (pin "1") (pinfunction "1_1") (pintype "passive"))
      (node (ref "C20") (pin "1") (pinfunction "1_1") (pintype "passive"))
      (node (ref "C21") (pin "1") (pinfunction "1_1") (pintype "passive"))
      (node (ref "C22") (pin "1") (pinfunction "1_1") (pintype "passive"))
      (node (ref "C23") (pin "1") (pinfunction "1_1") (pintype "passive"))
      (node (ref "C24") (pin "1") (pinfunction "1_1") (pintype "passive"))
      (node (ref "C25") (pin "1") (pinfunction "1_1") (pintype "passive"))
      (node (ref "C26") (pin "1") (pinfunction "1_1") (pintype "passive"))
      (node (ref "C27") (pin "2") (pinfunction "2_2") (pintype "passive"))
      (node (ref "C28") (pin "1") (pinfunction "1_1") (pintype "passive"))
      (node (ref "C29") (pin "1") (pinfunction "1_1") (pintype "passive"))
      (node (ref "C3") (pin "2") (pinfunction "2_2") (pintype "passive"))
      (node (ref "C30") (pin "1") (pinfunction "1_1") (pintype "passive"))
      (node (ref "C31") (pin "1") (pinfunction "1_1") (pintype "passive"))
      (node (ref "C32") (pin "1") (pinfunction "1_1") (pintype "passive"))
      (node (ref "C33") (pin "1") (pinfunction "1_1") (pintype "passive"))
      (node (ref "C34") (pin "1") (pinfunction "1_1") (pintype "passive"))
      (node (ref "C36") (pin "1") (pinfunction "1_1") (pintype "passive"))
      (node (ref "C37") (pin "1") (pinfunction "1_1") (pintype "passive"))
      (node (ref "C38") (pin "1") (pinfunction "1_1") (pintype "passive"))
      (node (ref "C39") (pin "1") (pinfunction "1_1") (pintype "passive"))
      (node (ref "C4") (pin "2") (pinfunction "2_2") (pintype "passive"))
      (node (ref "C40") (pin "1") (pinfunction "1_1") (pintype "passive"))
      (node (ref "C41") (pin "1") (pinfunction "1_1") (pintype "passive"))
      (node (ref "C42") (pin "1") (pinfunction "1_1") (pintype "passive"))
      (node (ref "C43") (pin "1") (pinfunction "1_1") (pintype "passive"))
      (node (ref "C44") (pin "1") (pinfunction "1_1") (pintype "passive"))
      (node (ref "C45") (pin "1") (pinfunction "1_1") (pintype "passive"))
      (node (ref "C46") (pin "1") (pinfunction "1_1") (pintype "passive"))
      (node (ref "C5") (pin "1") (pinfunction "1_1") (pintype "passive"))
      (node (ref "C6") (pin "1") (pinfunction "1_1") (pintype "passive"))
      (node (ref "C7") (pin "1") (pinfunction "1_1") (pintype "passive"))
      (node (ref "C8") (pin "2") (pinfunction "2_2") (pintype "passive"))
      (node (ref "C9") (pin "1") (pinfunction "1_1") (pintype "passive"))
      (node (ref "IC2") (pin "1") (pinfunction "GND_1") (pintype "power_in"))
      (node (ref "LED_R1C1") (pin "GND") (pinfunction "GND_GND") (pintype "power_in"))
      (node (ref "LED_R1C2") (pin "GND") (pinfunction "GND_GND") (pintype "power_in"))
      (node (ref "LED_R1C3") (pin "GND") (pinfunction "GND_GND") (pintype "power_in"))
      (node (ref "LED_R1C4") (pin "GND") (pinfunction "GND_GND") (pintype "power_in"))
      (node (ref "LED_R2C1") (pin "GND") (pinfunction "GND_GND") (pintype "power_in"))
      (node (ref "LED_R2C2") (pin "GND") (pinfunction "GND_GND") (pintype "power_in"))
      (node (ref "LED_R2C3") (pin "GND") (pinfunction "GND_GND") (pintype "power_in"))
      (node (ref "LED_R2C4") (pin "GND") (pinfunction "GND_GND") (pintype "power_in"))
      (node (ref "LED_R3C1") (pin "GND") (pinfunction "GND_GND") (pintype "power_in"))
      (node (ref "LED_R3C2") (pin "GND") (pinfunction "GND_GND") (pintype "power_in"))
      (node (ref "LED_R3C3") (pin "GND") (pinfunction "GND_GND") (pintype "power_in"))
      (node (ref "LED_R3C4") (pin "GND") (pinfunction "GND_GND") (pintype "power_in"))
      (node (ref "LED_R4C1") (pin "GND") (pinfunction "GND_GND") (pintype "power_in"))
      (node (ref "LED_R4C2") (pin "GND") (pinfunction "GND_GND") (pintype "power_in"))
      (node (ref "LED_R4C3") (pin "GND") (pinfunction "GND_GND") (pintype "power_in"))
      (node (ref "LED_R4C4") (pin "GND") (pinfunction "GND_GND") (pintype "power_in"))
      (node (ref "LED_R5C1") (pin "GND") (pinfunction "GND_GND") (pintype "power_in"))
      (node (ref "LED_R5C2") (pin "GND") (pinfunction "GND_GND") (pintype "power_in"))
      (node (ref "LED_R5C3") (pin "GND") (pinfunction "GND_GND") (pintype "power_in"))
      (node (ref "LED_R5C4") (pin "GND") (pinfunction "GND_GND") (pintype "power_in"))
      (node (ref "R1") (pin "2") (pinfunction "2_2") (pintype "passive"))
      (node (ref "R10") (pin "2") (pinfunction "2_2") (pintype "passive"))
      (node (ref "R17") (pin "1") (pinfunction "1_1") (pintype "passive"))
      (node (ref "R5") (pin "1") (pinfunction "1_1") (pintype "passive"))
      (node (ref "R6") (pin "1") (pinfunction "1_1") (pintype "passive"))
      (node (ref "R9") (pin "2") (pinfunction "2_2") (pintype "passive"))
      (node (ref "SD1") (pin "6") (pinfunction "VSS_6") (pintype "power_in"))
      (node (ref "SD1") (pin "S1") (pinfunction "S1_S1") (pintype "passive"))
      (node (ref "SD1") (pin "S2") (pinfunction "S2_S2") (pintype "passive"))
      (node (ref "SD1") (pin "S3") (pinfunction "S3_S3") (pintype "passive"))
      (node (ref "SD1") (pin "S4") (pinfunction "S4_S4") (pintype "passive"))
      (node (ref "SW1") (pin "A") (pinfunction "P_A") (pintype "passive"))
      (node (ref "SW1") (pin "A'") (pinfunction "P1_A'") (pintype "passive"))
      (node (ref "SW2") (pin "A") (pinfunction "P_A") (pintype "passive"))
      (node (ref "SW2") (pin "A'") (pinfunction "P1_A'") (pintype "passive"))
      (node (ref "SW21") (pin "C") (pinfunction "C_C") (pintype "passive"))
      (node (ref "SW21") (pin "E") (pinfunction "2_E") (pintype "passive"))
      (node (ref "SW22") (pin "C") (pinfunction "C_C") (pintype "passive"))
      (node (ref "SW22") (pin "E") (pinfunction "2_E") (pintype "passive"))
      (node (ref "SW3") (pin "P$1") (pinfunction "1_P$1") (pintype "bidirectional"))
      (node (ref "SW3") (pin "P$4") (pinfunction "4_P$4") (pintype "bidirectional"))
      (node (ref "SW4") (pin "P$1") (pinfunction "1_P$1") (pintype "bidirectional"))
      (node (ref "SW4") (pin "P$4") (pinfunction "4_P$4") (pintype "bidirectional"))
      (node (ref "U$19") (pin "2") (pinfunction "GND_2") (pintype "bidirectional"))
      (node (ref "U$2") (pin "1") (pinfunction "GND_1") (pintype "bidirectional"))
      (node (ref "U$2") (pin "12") (pinfunction "GND2_12") (pintype "bidirectional"))
      (node (ref "U$2") (pin "31") (pinfunction "SHIELD_31") (pintype "bidirectional"))
      (node (ref "U$2") (pin "32") (pinfunction "SHIELD_32") (pintype "bidirectional"))
      (node (ref "U$3") (pin "2") (pinfunction "2_2") (pintype "passive"))
      (node (ref "U$3") (pin "FIT@1") (pinfunction "11_FIT@1") (pintype "passive"))
      (node (ref "U$3") (pin "FIT@2") (pinfunction "12_FIT@2") (pintype "passive"))
      (node (ref "U1") (pin "A1B12") (pinfunction "GND_A1B12") (pintype "bidirectional"))
      (node (ref "U1") (pin "B11A12") (pinfunction "GND_B11A12") (pintype "bidirectional"))
      (node (ref "U1") (pin "P$13") (pinfunction "GND_P$13") (pintype "bidirectional"))
      (node (ref "U1") (pin "P$14") (pinfunction "GND_P$14") (pintype "bidirectional"))
      (node (ref "U1") (pin "P$15") (pinfunction "GND_P$15") (pintype "bidirectional"))
      (node (ref "U1") (pin "P$16") (pinfunction "GND_P$16") (pintype "bidirectional"))
      (node (ref "U2") (pin "A1B12") (pinfunction "GND_A1B12") (pintype "bidirectional"))
      (node (ref "U2") (pin "B11A12") (pinfunction "GND_B11A12") (pintype "bidirectional"))
      (node (ref "U2") (pin "P$13") (pinfunction "GND_P$13") (pintype "bidirectional"))
      (node (ref "U2") (pin "P$14") (pinfunction "GND_P$14") (pintype "bidirectional"))
      (node (ref "U2") (pin "P$15") (pinfunction "GND_P$15") (pintype "bidirectional"))
      (node (ref "U2") (pin "P$16") (pinfunction "GND_P$16") (pintype "bidirectional"))
      (node (ref "U3") (pin "57") (pinfunction "GND_57") (pintype "power_in"))
      (node (ref "U5") (pin "4") (pinfunction "GND_4") (pintype "bidirectional"))
      (node (ref "X1") (pin "1") (pinfunction "GND_1") (pintype "passive"))
      (node (ref "X1") (pin "2") (pinfunction "GND_2") (pintype "passive"))
      (node (ref "X2") (pin "1") (pinfunction "GND_1") (pintype "passive"))
      (node (ref "X2") (pin "2") (pinfunction "GND_2") (pintype "passive"))
      (node (ref "Y1") (pin "2") (pinfunction "3_2") (pintype "passive"))
      (node (ref "Y1") (pin "4") (pinfunction "3_4") (pintype "passive"))
    )
    (net (code "19") (name "MOSI") (class "Default")
      (node (ref "U$2") (pin "10") (pinfunction "D1_10") (pintype "bidirectional"))
      (node (ref "U3") (pin "15") (pinfunction "GPIO10_15") (pintype "bidirectional"))
    )
    (net (code "20") (name "Net-(IC2-VIN)") (class "Default")
      (node (ref "C29") (pin "2") (pinfunction "2_2") (pintype "passive"))
      (node (ref "IC2") (pin "3") (pinfunction "VIN_3") (pintype "input"))
      (node (ref "JP2") (pin "2") (pinfunction "2_2") (pintype "passive"))
      (node (ref "U$3") (pin "1") (pinfunction "1_1") (pintype "passive"))
      (node (ref "U1") (pin "A4B9") (pinfunction "VBUS_A4B9") (pintype "bidirectional"))
      (node (ref "U1") (pin "B4A9") (pinfunction "VBUS_B4A9") (pintype "bidirectional"))
    )
    (net (code "21") (name "Net-(JP2-Pad1)") (class "Default")
      (node (ref "JP2") (pin "1") (pinfunction "1_1") (pintype "passive"))
      (node (ref "U2") (pin "A4B9") (pinfunction "VBUS_A4B9") (pintype "bidirectional"))
      (node (ref "U2") (pin "B4A9") (pinfunction "VBUS_B4A9") (pintype "bidirectional"))
    )
    (net (code "22") (name "Net-(LED_R1C1-DI)") (class "Default")
      (node (ref "LED_R1C1") (pin "DIN") (pinfunction "DI_DIN") (pintype "input"))
      (node (ref "LED_R1C2") (pin "DOUT") (pinfunction "DO_DOUT") (pintype "output"))
    )
    (net (code "23") (name "Net-(LED_R1C1-DO)") (class "Default")
      (node (ref "LED_R1C1") (pin "DOUT") (pinfunction "DO_DOUT") (pintype "output"))
      (node (ref "LED_R2C1") (pin "DIN") (pinfunction "DI_DIN") (pintype "input"))
    )
    (net (code "24") (name "Net-(LED_R1C2-DI)") (class "Default")
      (node (ref "LED_R1C2") (pin "DIN") (pinfunction "DI_DIN") (pintype "input"))
      (node (ref "LED_R1C3") (pin "DOUT") (pinfunction "DO_DOUT") (pintype "output"))
    )
    (net (code "25") (name "Net-(LED_R1C3-DI)") (class "Default")
      (node (ref "LED_R1C3") (pin "DIN") (pinfunction "DI_DIN") (pintype "input"))
      (node (ref "LED_R1C4") (pin "DOUT") (pinfunction "DO_DOUT") (pintype "output"))
    )
    (net (code "26") (name "Net-(LED_R1C4-DI)") (class "Default")
      (node (ref "LED_R1C4") (pin "DIN") (pinfunction "DI_DIN") (pintype "input"))
      (node (ref "R5") (pin "2") (pinfunction "2_2") (pintype "passive"))
      (node (ref "U3") (pin "52") (pinfunction "GPIO46_52") (pintype "bidirectional"))
    )
    (net (code "27") (name "Net-(LED_R2C1-DO)") (class "Default")
      (node (ref "LED_R2C1") (pin "DOUT") (pinfunction "DO_DOUT") (pintype "output"))
      (node (ref "LED_R2C2") (pin "DIN") (pinfunction "DI_DIN") (pintype "input"))
    )
    (net (code "28") (name "Net-(LED_R2C2-DO)") (class "Default")
      (node (ref "LED_R2C2") (pin "DOUT") (pinfunction "DO_DOUT") (pintype "output"))
      (node (ref "LED_R2C3") (pin "DIN") (pinfunction "DI_DIN") (pintype "input"))
    )
    (net (code "29") (name "Net-(LED_R2C3-DO)") (class "Default")
      (node (ref "LED_R2C3") (pin "DOUT") (pinfunction "DO_DOUT") (pintype "output"))
      (node (ref "LED_R2C4") (pin "DIN") (pinfunction "DI_DIN") (pintype "input"))
    )
    (net (code "30") (name "Net-(LED_R2C4-DO)") (class "Default")
      (node (ref "LED_R2C4") (pin "DOUT") (pinfunction "DO_DOUT") (pintype "output"))
      (node (ref "LED_R3C4") (pin "DIN") (pinfunction "DI_DIN") (pintype "input"))
    )
    (net (code "31") (name "Net-(LED_R3C1-DI)") (class "Default")
      (node (ref "LED_R3C1") (pin "DIN") (pinfunction "DI_DIN") (pintype "input"))
      (node (ref "LED_R3C2") (pin "DOUT") (pinfunction "DO_DOUT") (pintype "output"))
    )
    (net (code "32") (name "Net-(LED_R3C1-DO)") (class "Default")
      (node (ref "LED_R3C1") (pin "DOUT") (pinfunction "DO_DOUT") (pintype "output"))
      (node (ref "LED_R4C1") (pin "DIN") (pinfunction "DI_DIN") (pintype "input"))
    )
    (net (code "33") (name "Net-(LED_R3C2-DI)") (class "Default")
      (node (ref "LED_R3C2") (pin "DIN") (pinfunction "DI_DIN") (pintype "input"))
      (node (ref "LED_R3C3") (pin "DOUT") (pinfunction "DO_DOUT") (pintype "output"))
    )
    (net (code "34") (name "Net-(LED_R3C3-DI)") (class "Default")
      (node (ref "LED_R3C3") (pin "DIN") (pinfunction "DI_DIN") (pintype "input"))
      (node (ref "LED_R3C4") (pin "DOUT") (pinfunction "DO_DOUT") (pintype "output"))
    )
    (net (code "35") (name "Net-(LED_R4C1-DO)") (class "Default")
      (node (ref "LED_R4C1") (pin "DOUT") (pinfunction "DO_DOUT") (pintype "output"))
      (node (ref "LED_R4C2") (pin "DIN") (pinfunction "DI_DIN") (pintype "input"))
    )
    (net (code "36") (name "Net-(LED_R4C2-DO)") (class "Default")
      (node (ref "LED_R4C2") (pin "DOUT") (pinfunction "DO_DOUT") (pintype "output"))
      (node (ref "LED_R4C3") (pin "DIN") (pinfunction "DI_DIN") (pintype "input"))
    )
    (net (code "37") (name "Net-(LED_R4C3-DO)") (class "Default")
      (node (ref "LED_R4C3") (pin "DOUT") (pinfunction "DO_DOUT") (pintype "output"))
      (node (ref "LED_R4C4") (pin "DIN") (pinfunction "DI_DIN") (pintype "input"))
    )
    (net (code "38") (name "Net-(LED_R4C4-DO)") (class "Default")
      (node (ref "LED_R4C4") (pin "DOUT") (pinfunction "DO_DOUT") (pintype "output"))
      (node (ref "LED_R5C4") (pin "DIN") (pinfunction "DI_DIN") (pintype "input"))
    )
    (net (code "39") (name "Net-(LED_R5C1-DI)") (class "Default")
      (node (ref "LED_R5C1") (pin "DIN") (pinfunction "DI_DIN") (pintype "input"))
      (node (ref "LED_R5C2") (pin "DOUT") (pinfunction "DO_DOUT") (pintype "output"))
    )
    (net (code "40") (name "Net-(LED_R5C2-DI)") (class "Default")
      (node (ref "LED_R5C2") (pin "DIN") (pinfunction "DI_DIN") (pintype "input"))
      (node (ref "LED_R5C3") (pin "DOUT") (pinfunction "DO_DOUT") (pintype "output"))
    )
    (net (code "41") (name "Net-(LED_R5C3-DI)") (class "Default")
      (node (ref "LED_R5C3") (pin "DIN") (pinfunction "DI_DIN") (pintype "input"))
      (node (ref "LED_R5C4") (pin "DOUT") (pinfunction "DO_DOUT") (pintype "output"))
    )
    (net (code "42") (name "Net-(R8-Pad2)") (class "Default")
      (node (ref "R8") (pin "2") (pinfunction "2_2") (pintype "passive"))
      (node (ref "SW22") (pin "A") (pinfunction "A_A") (pintype "passive"))
    )
    (net (code "43") (name "Net-(R13-Pad2)") (class "Default")
      (node (ref "R13") (pin "2") (pinfunction "2_2") (pintype "passive"))
      (node (ref "SW22") (pin "B") (pinfunction "B_B") (pintype "passive"))
    )
    (net (code "44") (name "Net-(R14-Pad2)") (class "Default")
      (node (ref "R14") (pin "2") (pinfunction "2_2") (pintype "passive"))
      (node (ref "SW21") (pin "A") (pinfunction "A_A") (pintype "passive"))
    )
    (net (code "45") (name "Net-(R15-Pad2)") (class "Default")
      (node (ref "R15") (pin "2") (pinfunction "2_2") (pintype "passive"))
      (node (ref "SW21") (pin "B") (pinfunction "B_B") (pintype "passive"))
    )
    (net (code "46") (name "Net-(SD1-CD{slash}DAT3(~{CS}))") (class "Default")
      (node (ref "R11") (pin "2") (pinfunction "2_2") (pintype "passive"))
      (node (ref "SD1") (pin "2") (pinfunction "CD/DAT3(~{CS})_2") (pintype "bidirectional"))
    )
    (net (code "47") (name "Net-(SW1-S)") (class "Default")
      (node (ref "SW1") (pin "B") (pinfunction "S_B") (pintype "passive"))
      (node (ref "SW1") (pin "B'") (pinfunction "S1_B'") (pintype "passive"))
      (node (ref "U3") (pin "23") (pinfunction "GPIO17_23") (pintype "bidirectional"))
    )
    (net (code "48") (name "Net-(SW2-S)") (class "Default")
      (node (ref "SW2") (pin "B") (pinfunction "S_B") (pintype "passive"))
      (node (ref "SW2") (pin "B'") (pinfunction "S1_B'") (pintype "passive"))
      (node (ref "U3") (pin "24") (pinfunction "GPIO18_24") (pintype "bidirectional"))
    )
    (net (code "49") (name "Net-(SW3-2)") (class "Default")
      (node (ref "C4") (pin "1") (pinfunction "1_1") (pintype "passive"))
      (node (ref "R19") (pin "2") (pinfunction "2_2") (pintype "passive"))
      (node (ref "R2") (pin "2") (pinfunction "2_2") (pintype "passive"))
      (node (ref "SW3") (pin "P$2") (pinfunction "2_P$2") (pintype "bidirectional"))
      (node (ref "SW3") (pin "P$3") (pinfunction "3_P$3") (pintype "bidirectional"))
      (node (ref "U3") (pin "4") (pinfunction "CHIP_PU_4") (pintype "input"))
    )
    (net (code "50") (name "Net-(SW21B-1)") (class "Default")
      (node (ref "R16") (pin "1") (pinfunction "1_1") (pintype "passive"))
      (node (ref "R19") (pin "1") (pinfunction "1_1") (pintype "passive"))
      (node (ref "SW21") (pin "D") (pinfunction "1_D") (pintype "passive"))
      (node (ref "U3") (pin "8") (pinfunction "GPIO3_8") (pintype "bidirectional"))
    )
    (net (code "51") (name "Net-(SW22B-1)") (class "Default")
      (node (ref "SW22") (pin "D") (pinfunction "1_D") (pintype "passive"))
      (node (ref "SW4") (pin "P$2") (pinfunction "2_P$2") (pintype "bidirectional"))
      (node (ref "SW4") (pin "P$3") (pinfunction "3_P$3") (pintype "bidirectional"))
      (node (ref "U3") (pin "5") (pinfunction "GPIO0_5") (pintype "bidirectional"))
    )
    (net (code "52") (name "Net-(SWR1C1-1)") (class "Default")
      (node (ref "D2") (pin "A") (pinfunction "A_A") (pintype "passive"))
      (node (ref "SWR1C1") (pin "2") (pinfunction "1_2") (pintype "passive"))
    )
    (net (code "53") (name "Net-(SWR1C2-1)") (class "Default")
      (node (ref "D3") (pin "A") (pinfunction "A_A") (pintype "passive"))
      (node (ref "SWR1C2") (pin "2") (pinfunction "1_2") (pintype "passive"))
    )
    (net (code "54") (name "Net-(SWR1C3-1)") (class "Default")
      (node (ref "D4") (pin "A") (pinfunction "A_A") (pintype "passive"))
      (node (ref "SWR1C3") (pin "2") (pinfunction "1_2") (pintype "passive"))
    )
    (net (code "55") (name "Net-(SWR1C4-1)") (class "Default")
      (node (ref "D5") (pin "A") (pinfunction "A_A") (pintype "passive"))
      (node (ref "SWR1C4") (pin "2") (pinfunction "1_2") (pintype "passive"))
    )
    (net (code "56") (name "Net-(SWR2C1-1)") (class "Default")
      (node (ref "D6") (pin "A") (pinfunction "A_A") (pintype "passive"))
      (node (ref "SWR2C1") (pin "2") (pinfunction "1_2") (pintype "passive"))
    )
    (net (code "57") (name "Net-(SWR2C2-1)") (class "Default")
      (node (ref "D7") (pin "A") (pinfunction "A_A") (pintype "passive"))
      (node (ref "SWR2C2") (pin "2") (pinfunction "1_2") (pintype "passive"))
    )
    (net (code "58") (name "Net-(SWR2C3-1)") (class "Default")
      (node (ref "D8") (pin "A") (pinfunction "A_A") (pintype "passive"))
      (node (ref "SWR2C3") (pin "2") (pinfunction "1_2") (pintype "passive"))
    )
    (net (code "59") (name "Net-(SWR2C4-1)") (class "Default")
      (node (ref "D9") (pin "A") (pinfunction "A_A") (pintype "passive"))
      (node (ref "SWR2C4") (pin "2") (pinfunction "1_2") (pintype "passive"))
    )
    (net (code "60") (name "Net-(SWR3C1-1)") (class "Default")
      (node (ref "D13") (pin "A") (pinfunction "A_A") (pintype "passive"))
      (node (ref "SWR3C1") (pin "2") (pinfunction "1_2") (pintype "passive"))
    )
    (net (code "61") (name "Net-(SWR3C2-1)") (class "Default")
      (node (ref "D12") (pin "A") (pinfunction "A_A") (pintype "passive"))
      (node (ref "SWR3C2") (pin "2") (pinfunction "1_2") (pintype "passive"))
    )
    (net (code "62") (name "Net-(SWR3C3-1)") (class "Default")
      (node (ref "D11") (pin "A") (pinfunction "A_A") (pintype "passive"))
      (node (ref "SWR3C3") (pin "2") (pinfunction "1_2") (pintype "passive"))
    )
    (net (code "63") (name "Net-(SWR3C4-1)") (class "Default")
      (node (ref "D10") (pin "A") (pinfunction "A_A") (pintype "passive"))
      (node (ref "SWR3C4") (pin "2") (pinfunction "1_2") (pintype "passive"))
    )
    (net (code "64") (name "Net-(SWR4C1-1)") (class "Default")
      (node (ref "D14") (pin "A") (pinfunction "A_A") (pintype "passive"))
      (node (ref "SWR4C1") (pin "2") (pinfunction "1_2") (pintype "passive"))
    )
    (net (code "65") (name "Net-(SWR4C2-1)") (class "Default")
      (node (ref "D15") (pin "A") (pinfunction "A_A") (pintype "passive"))
      (node (ref "SWR4C2") (pin "2") (pinfunction "1_2") (pintype "passive"))
    )
    (net (code "66") (name "Net-(SWR4C3-1)") (class "Default")
      (node (ref "D16") (pin "A") (pinfunction "A_A") (pintype "passive"))
      (node (ref "SWR4C3") (pin "2") (pinfunction "1_2") (pintype "passive"))
    )
    (net (code "67") (name "Net-(SWR4C4-1)") (class "Default")
      (node (ref "D17") (pin "A") (pinfunction "A_A") (pintype "passive"))
      (node (ref "SWR4C4") (pin "2") (pinfunction "1_2") (pintype "passive"))
    )
    (net (code "68") (name "Net-(SWR5C1-1)") (class "Default")
      (node (ref "D21") (pin "A") (pinfunction "A_A") (pintype "passive"))
      (node (ref "SWR5C1") (pin "2") (pinfunction "1_2") (pintype "passive"))
    )
    (net (code "69") (name "Net-(SWR5C2-1)") (class "Default")
      (node (ref "D20") (pin "A") (pinfunction "A_A") (pintype "passive"))
      (node (ref "SWR5C2") (pin "2") (pinfunction "1_2") (pintype "passive"))
    )
    (net (code "70") (name "Net-(SWR5C3-1)") (class "Default")
      (node (ref "D19") (pin "A") (pinfunction "A_A") (pintype "passive"))
      (node (ref "SWR5C3") (pin "2") (pinfunction "1_2") (pintype "passive"))
    )
    (net (code "71") (name "Net-(SWR5C4-1)") (class "Default")
      (node (ref "D18") (pin "A") (pinfunction "A_A") (pintype "passive"))
      (node (ref "SWR5C4") (pin "2") (pinfunction "1_2") (pintype "passive"))
    )
    (net (code "72") (name "Net-(U$2-IREF)") (class "Default")
      (node (ref "R6") (pin "2") (pinfunction "2_2") (pintype "passive"))
      (node (ref "U$2") (pin "5") (pinfunction "IREF_5") (pintype "bidirectional"))
    )
    (net (code "73") (name "Net-(U$2-VCOMH)") (class "Default")
      (node (ref "C34") (pin "2") (pinfunction "2_2") (pintype "passive"))
      (node (ref "U$2") (pin "3") (pinfunction "VCOMH_3") (pintype "bidirectional"))
    )
    (net (code "74") (name "Net-(U$19-FB)") (class "Default")
      (node (ref "C35") (pin "1") (pinfunction "1_1") (pintype "passive"))
      (node (ref "R10") (pin "1") (pinfunction "1_1") (pintype "passive"))
      (node (ref "R7") (pin "2") (pinfunction "2_2") (pintype "passive"))
      (node (ref "U$19") (pin "3") (pinfunction "FB_3") (pintype "bidirectional"))
    )
    (net (code "75") (name "Net-(U$19-SW)") (class "Default")
      (node (ref "D1") (pin "A") (pinfunction "A_A") (pintype "passive"))
      (node (ref "L2") (pin "2") (pinfunction "2_2") (pintype "passive"))
      (node (ref "U$19") (pin "1") (pinfunction "SW_1") (pintype "bidirectional"))
    )
    (net (code "76") (name "Net-(U1-CC1)") (class "Default")
      (node (ref "R4") (pin "2") (pinfunction "2_2") (pintype "passive"))
      (node (ref "U1") (pin "A5") (pinfunction "CC1_A5") (pintype "bidirectional"))
    )
    (net (code "77") (name "Net-(U1-CC2)") (class "Default")
      (node (ref "R18") (pin "2") (pinfunction "2_2") (pintype "passive"))
      (node (ref "U1") (pin "B5") (pinfunction "CC2_B5") (pintype "bidirectional"))
    )
    (net (code "78") (name "Net-(U2-CC1)") (class "Default")
      (node (ref "R9") (pin "1") (pinfunction "1_1") (pintype "passive"))
      (node (ref "U2") (pin "A5") (pinfunction "CC1_A5") (pintype "bidirectional"))
    )
    (net (code "79") (name "Net-(U2-CC2)") (class "Default")
      (node (ref "R1") (pin "1") (pinfunction "1_1") (pintype "passive"))
      (node (ref "U2") (pin "B5") (pinfunction "CC2_B5") (pintype "bidirectional"))
    )
    (net (code "80") (name "Net-(U3-GPIO1)") (class "Default")
      (node (ref "C1") (pin "2") (pinfunction "2_2") (pintype "passive"))
      (node (ref "R8") (pin "1") (pinfunction "1_1") (pintype "passive"))
      (node (ref "U3") (pin "6") (pinfunction "GPIO1_6") (pintype "bidirectional"))
    )
    (net (code "81") (name "Net-(U3-GPIO2)") (class "Default")
      (node (ref "C2") (pin "2") (pinfunction "2_2") (pintype "passive"))
      (node (ref "R13") (pin "1") (pinfunction "1_1") (pintype "passive"))
      (node (ref "U3") (pin "7") (pinfunction "GPIO2_7") (pintype "bidirectional"))
    )
    (net (code "82") (name "Net-(U3-GPIO4)") (class "Default")
      (node (ref "C9") (pin "2") (pinfunction "2_2") (pintype "passive"))
      (node (ref "R14") (pin "1") (pinfunction "1_1") (pintype "passive"))
      (node (ref "U3") (pin "9") (pinfunction "GPIO4_9") (pintype "bidirectional"))
    )
    (net (code "83") (name "Net-(U3-GPIO5)") (class "Default")
      (node (ref "C10") (pin "2") (pinfunction "2_2") (pintype "passive"))
      (node (ref "R15") (pin "1") (pinfunction "1_1") (pintype "passive"))
      (node (ref "U3") (pin "10") (pinfunction "GPIO5_10") (pintype "bidirectional"))
    )
    (net (code "84") (name "Net-(U3-GPIO33)") (class "Default")
      (node (ref "U$3") (pin "7") (pinfunction "7_7") (pintype "passive"))
      (node (ref "U3") (pin "38") (pinfunction "GPIO33_38") (pintype "bidirectional"))
    )
    (net (code "85") (name "Net-(U3-GPIO34)") (class "Default")
      (node (ref "U$3") (pin "8") (pinfunction "8_8") (pintype "passive"))
      (node (ref "U3") (pin "39") (pinfunction "GPIO34_39") (pintype "bidirectional"))
    )
    (net (code "86") (name "Net-(U3-LNA_IN)") (class "Default")
      (node (ref "U3") (pin "1") (pinfunction "LNA_IN_1") (pintype "bidirectional"))
      (node (ref "X1") (pin "3") (pinfunction "SIGNAL_3") (pintype "passive"))
    )
    (net (code "87") (name "Net-(U3-SPICLK)") (class "Default")
      (node (ref "U3") (pin "33") (pinfunction "SPICLK_33") (pintype "bidirectional"))
      (node (ref "U5") (pin "6") (pinfunction "SCK_6") (pintype "bidirectional"))
    )
    (net (code "88") (name "Net-(U3-SPICLK_N)") (class "Default")
      (node (ref "U$3") (pin "5") (pinfunction "5_5") (pintype "passive"))
      (node (ref "U3") (pin "36") (pinfunction "SPICLK_N_36") (pintype "bidirectional"))
    )
    (net (code "89") (name "Net-(U3-SPICLK_P)") (class "Default")
      (node (ref "U$3") (pin "6") (pinfunction "6_6") (pintype "passive"))
      (node (ref "U3") (pin "37") (pinfunction "SPICLK_P_37") (pintype "bidirectional"))
    )
    (net (code "90") (name "Net-(U3-SPICS0)") (class "Default")
      (node (ref "U3") (pin "32") (pinfunction "SPICS0_32") (pintype "bidirectional"))
      (node (ref "U5") (pin "1") (pinfunction "~{CS}_1") (pintype "bidirectional"))
    )
    (net (code "91") (name "Net-(U3-SPID)") (class "Default")
      (node (ref "U3") (pin "35") (pinfunction "SPID_35") (pintype "bidirectional"))
      (node (ref "U5") (pin "5") (pinfunction "SI(D0)_5") (pintype "bidirectional"))
    )
    (net (code "92") (name "Net-(U3-SPIHD)") (class "Default")
      (node (ref "U3") (pin "30") (pinfunction "SPIHD_30") (pintype "bidirectional"))
      (node (ref "U5") (pin "7") (pinfunction "~{HOLD}(D3)_7") (pintype "bidirectional"))
    )
    (net (code "93") (name "Net-(U3-SPIQ)") (class "Default")
      (node (ref "U3") (pin "34") (pinfunction "SPIQ_34") (pintype "bidirectional"))
      (node (ref "U5") (pin "2") (pinfunction "SO(D1)_2") (pintype "bidirectional"))
    )
    (net (code "94") (name "Net-(U3-SPIWP)") (class "Default")
      (node (ref "U3") (pin "31") (pinfunction "SPIWP_31") (pintype "bidirectional"))
      (node (ref "U5") (pin "3") (pinfunction "~{WP}(D2)_3") (pintype "bidirectional"))
    )
    (net (code "95") (name "Net-(U3-U0RXD)") (class "Default")
      (node (ref "U$3") (pin "9") (pinfunction "9_9") (pintype "passive"))
      (node (ref "U3") (pin "50") (pinfunction "U0RXD_50") (pintype "bidirectional"))
    )
    (net (code "96") (name "Net-(U3-U0TXD)") (class "Default")
      (node (ref "JP3") (pin "1") (pinfunction "1_1") (pintype "passive"))
      (node (ref "U$3") (pin "10") (pinfunction "10_10") (pintype "passive"))
      (node (ref "U3") (pin "49") (pinfunction "U0TXD_49") (pintype "bidirectional"))
    )
    (net (code "97") (name "Net-(U3-XTAL_N)") (class "Default")
      (node (ref "C3") (pin "1") (pinfunction "1_1") (pintype "passive"))
      (node (ref "U3") (pin "53") (pinfunction "XTAL_N_53") (pintype "output"))
      (node (ref "Y1") (pin "3") (pinfunction "2_3") (pintype "passive"))
    )
    (net (code "98") (name "Net-(U3-XTAL_P)") (class "Default")
      (node (ref "C8") (pin "1") (pinfunction "1_1") (pintype "passive"))
      (node (ref "U3") (pin "54") (pinfunction "XTAL_P_54") (pintype "input"))
      (node (ref "Y1") (pin "1") (pinfunction "1_1") (pintype "passive"))
    )
    (net (code "99") (name "Net-(X2-SIGNAL)") (class "Default")
      (node (ref "R3") (pin "1") (pinfunction "1_1") (pintype "passive"))
      (node (ref "X2") (pin "3") (pinfunction "SIGNAL_3") (pintype "passive"))
    )
    (net (code "100") (name "OLED_CS") (class "Default")
      (node (ref "R12") (pin "1") (pinfunction "1_1") (pintype "passive"))
      (node (ref "U$2") (pin "6") (pinfunction "CS_6") (pintype "bidirectional"))
      (node (ref "U3") (pin "19") (pinfunction "GPIO14_19") (pintype "bidirectional"))
    )
    (net (code "101") (name "OLED_RESET") (class "Default")
      (node (ref "R17") (pin "2") (pinfunction "2_2") (pintype "passive"))
      (node (ref "U$2") (pin "7") (pinfunction "RES_7") (pintype "bidirectional"))
      (node (ref "U3") (pin "18") (pinfunction "GPIO13_18") (pintype "bidirectional"))
    )
    (net (code "102") (name "ROW0") (class "Default")
      (node (ref "D2") (pin "C") (pinfunction "C_C") (pintype "passive"))
      (node (ref "D3") (pin "C") (pinfunction "C_C") (pintype "passive"))
      (node (ref "D4") (pin "C") (pinfunction "C_C") (pintype "passive"))
      (node (ref "D5") (pin "C") (pinfunction "C_C") (pintype "passive"))
      (node (ref "U3") (pin "51") (pinfunction "GPIO45_51") (pintype "bidirectional"))
    )
    (net (code "103") (name "ROW1") (class "Default")
      (node (ref "D6") (pin "C") (pinfunction "C_C") (pintype "passive"))
      (node (ref "D7") (pin "C") (pinfunction "C_C") (pintype "passive"))
      (node (ref "D8") (pin "C") (pinfunction "C_C") (pintype "passive"))
      (node (ref "D9") (pin "C") (pinfunction "C_C") (pintype "passive"))
      (node (ref "U3") (pin "45") (pinfunction "MTDO_45") (pintype "bidirectional"))
    )
    (net (code "104") (name "ROW2") (class "Default")
      (node (ref "D10") (pin "C") (pinfunction "C_C") (pintype "passive"))
      (node (ref "D11") (pin "C") (pinfunction "C_C") (pintype "passive"))
      (node (ref "D12") (pin "C") (pinfunction "C_C") (pintype "passive"))
      (node (ref "D13") (pin "C") (pinfunction "C_C") (pintype "passive"))
      (node (ref "U3") (pin "42") (pinfunction "GPIO37_42") (pintype "bidirectional"))
    )
    (net (code "105") (name "ROW3") (class "Default")
      (node (ref "D14") (pin "C") (pinfunction "C_C") (pintype "passive"))
      (node (ref "D15") (pin "C") (pinfunction "C_C") (pintype "passive"))
      (node (ref "D16") (pin "C") (pinfunction "C_C") (pintype "passive"))
      (node (ref "D17") (pin "C") (pinfunction "C_C") (pintype "passive"))
      (node (ref "U3") (pin "41") (pinfunction "GPIO36_41") (pintype "bidirectional"))
    )
    (net (code "106") (name "ROW4") (class "Default")
      (node (ref "D18") (pin "C") (pinfunction "C_C") (pintype "passive"))
      (node (ref "D19") (pin "C") (pinfunction "C_C") (pintype "passive"))
      (node (ref "D20") (pin "C") (pinfunction "C_C") (pintype "passive"))
      (node (ref "D21") (pin "C") (pinfunction "C_C") (pintype "passive"))
      (node (ref "U3") (pin "40") (pinfunction "GPIO35_40") (pintype "bidirectional"))
    )
    (net (code "107") (name "SCLK") (class "Default")
      (node (ref "U$2") (pin "9") (pinfunction "D0_9") (pintype "bidirectional"))
      (node (ref "U3") (pin "16") (pinfunction "GPIO11_16") (pintype "bidirectional"))
    )
    (net (code "108") (name "unconnected-(JP2-Pad3)") (class "Default")
      (node (ref "JP2") (pin "3") (pinfunction "3_3") (pintype "passive"))
    )
    (net (code "109") (name "unconnected-(LED_R5C1-DO-PadDOUT)") (class "Default")
      (node (ref "LED_R5C1") (pin "DOUT") (pinfunction "DO_DOUT") (pintype "output"))
    )
    (net (code "110") (name "unconnected-(R3-Pad2)") (class "Default")
      (node (ref "R3") (pin "2") (pinfunction "2_2") (pintype "passive"))
    )
    (net (code "111") (name "unconnected-(SD1-DAT1-Pad8)") (class "Default")
      (node (ref "SD1") (pin "8") (pinfunction "DAT1_8") (pintype "bidirectional"))
    )
    (net (code "112") (name "unconnected-(SD1-DAT2-Pad1)") (class "Default")
      (node (ref "SD1") (pin "1") (pinfunction "DAT2_1") (pintype "bidirectional"))
    )
    (net (code "113") (name "unconnected-(U1-SBU1-PadA8)") (class "Default")
      (node (ref "U1") (pin "A8") (pinfunction "SBU1_A8") (pintype "bidirectional"))
    )
    (net (code "114") (name "unconnected-(U1-SBU2-PadB8)") (class "Default")
      (node (ref "U1") (pin "B8") (pinfunction "SBU2_B8") (pintype "bidirectional"))
    )
    (net (code "115") (name "unconnected-(U2-SBU1-PadA8)") (class "Default")
      (node (ref "U2") (pin "A8") (pinfunction "SBU1_A8") (pintype "bidirectional"))
    )
    (net (code "116") (name "unconnected-(U2-SBU2-PadB8)") (class "Default")
      (node (ref "U2") (pin "B8") (pinfunction "SBU2_B8") (pintype "bidirectional"))
    )
    (net (code "117") (name "unconnected-(U3-SPICS1-Pad28)") (class "Default")
      (node (ref "U3") (pin "28") (pinfunction "SPICS1_28") (pintype "bidirectional"))
    )
  )
)
